# 1_0v.net
KiCad netlist of a schematic drawn in Altium Designer
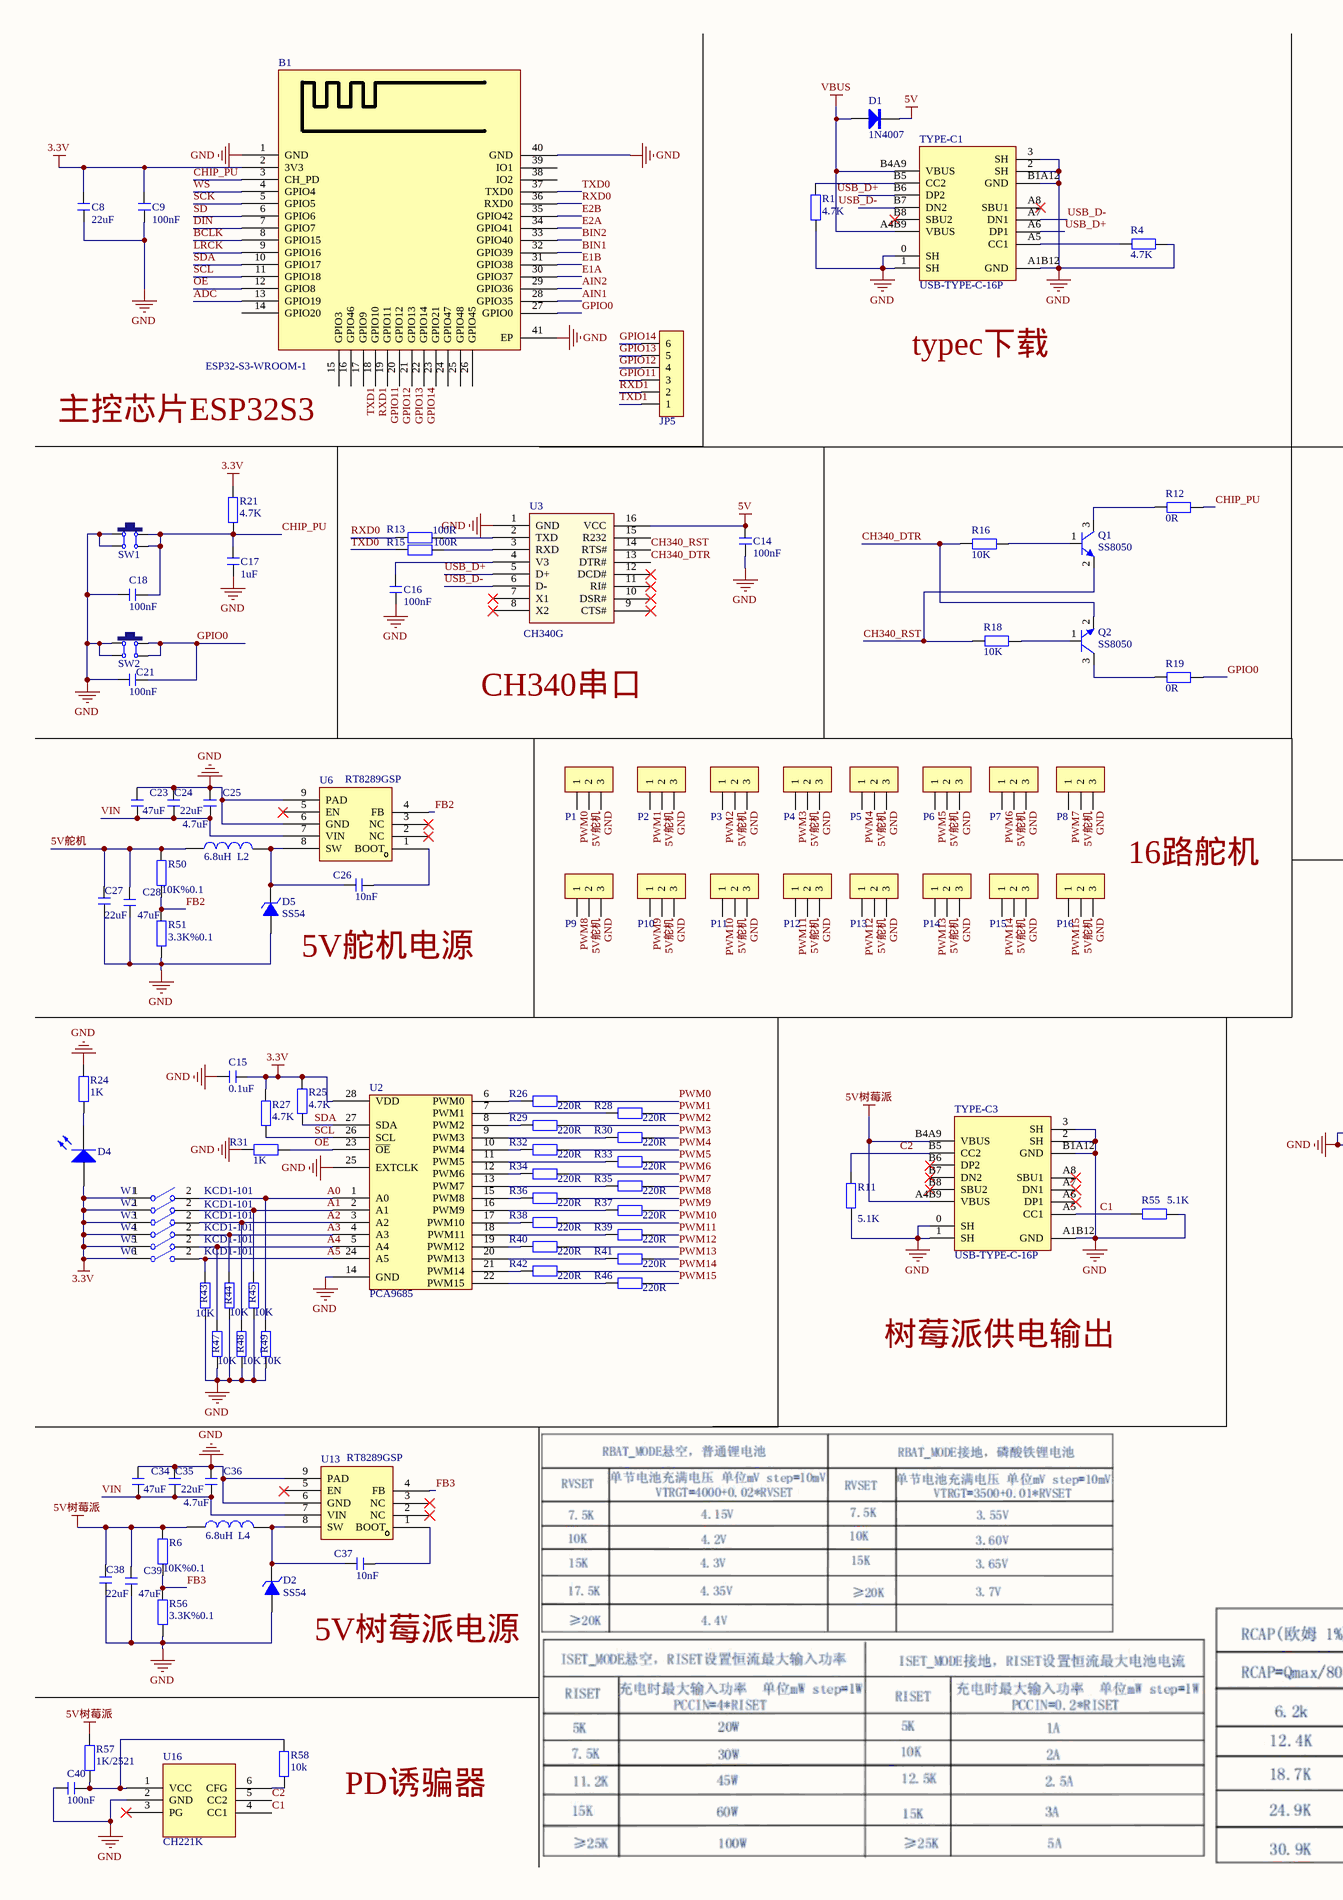
[diagram p0: 1.0v.SchDoc, left]
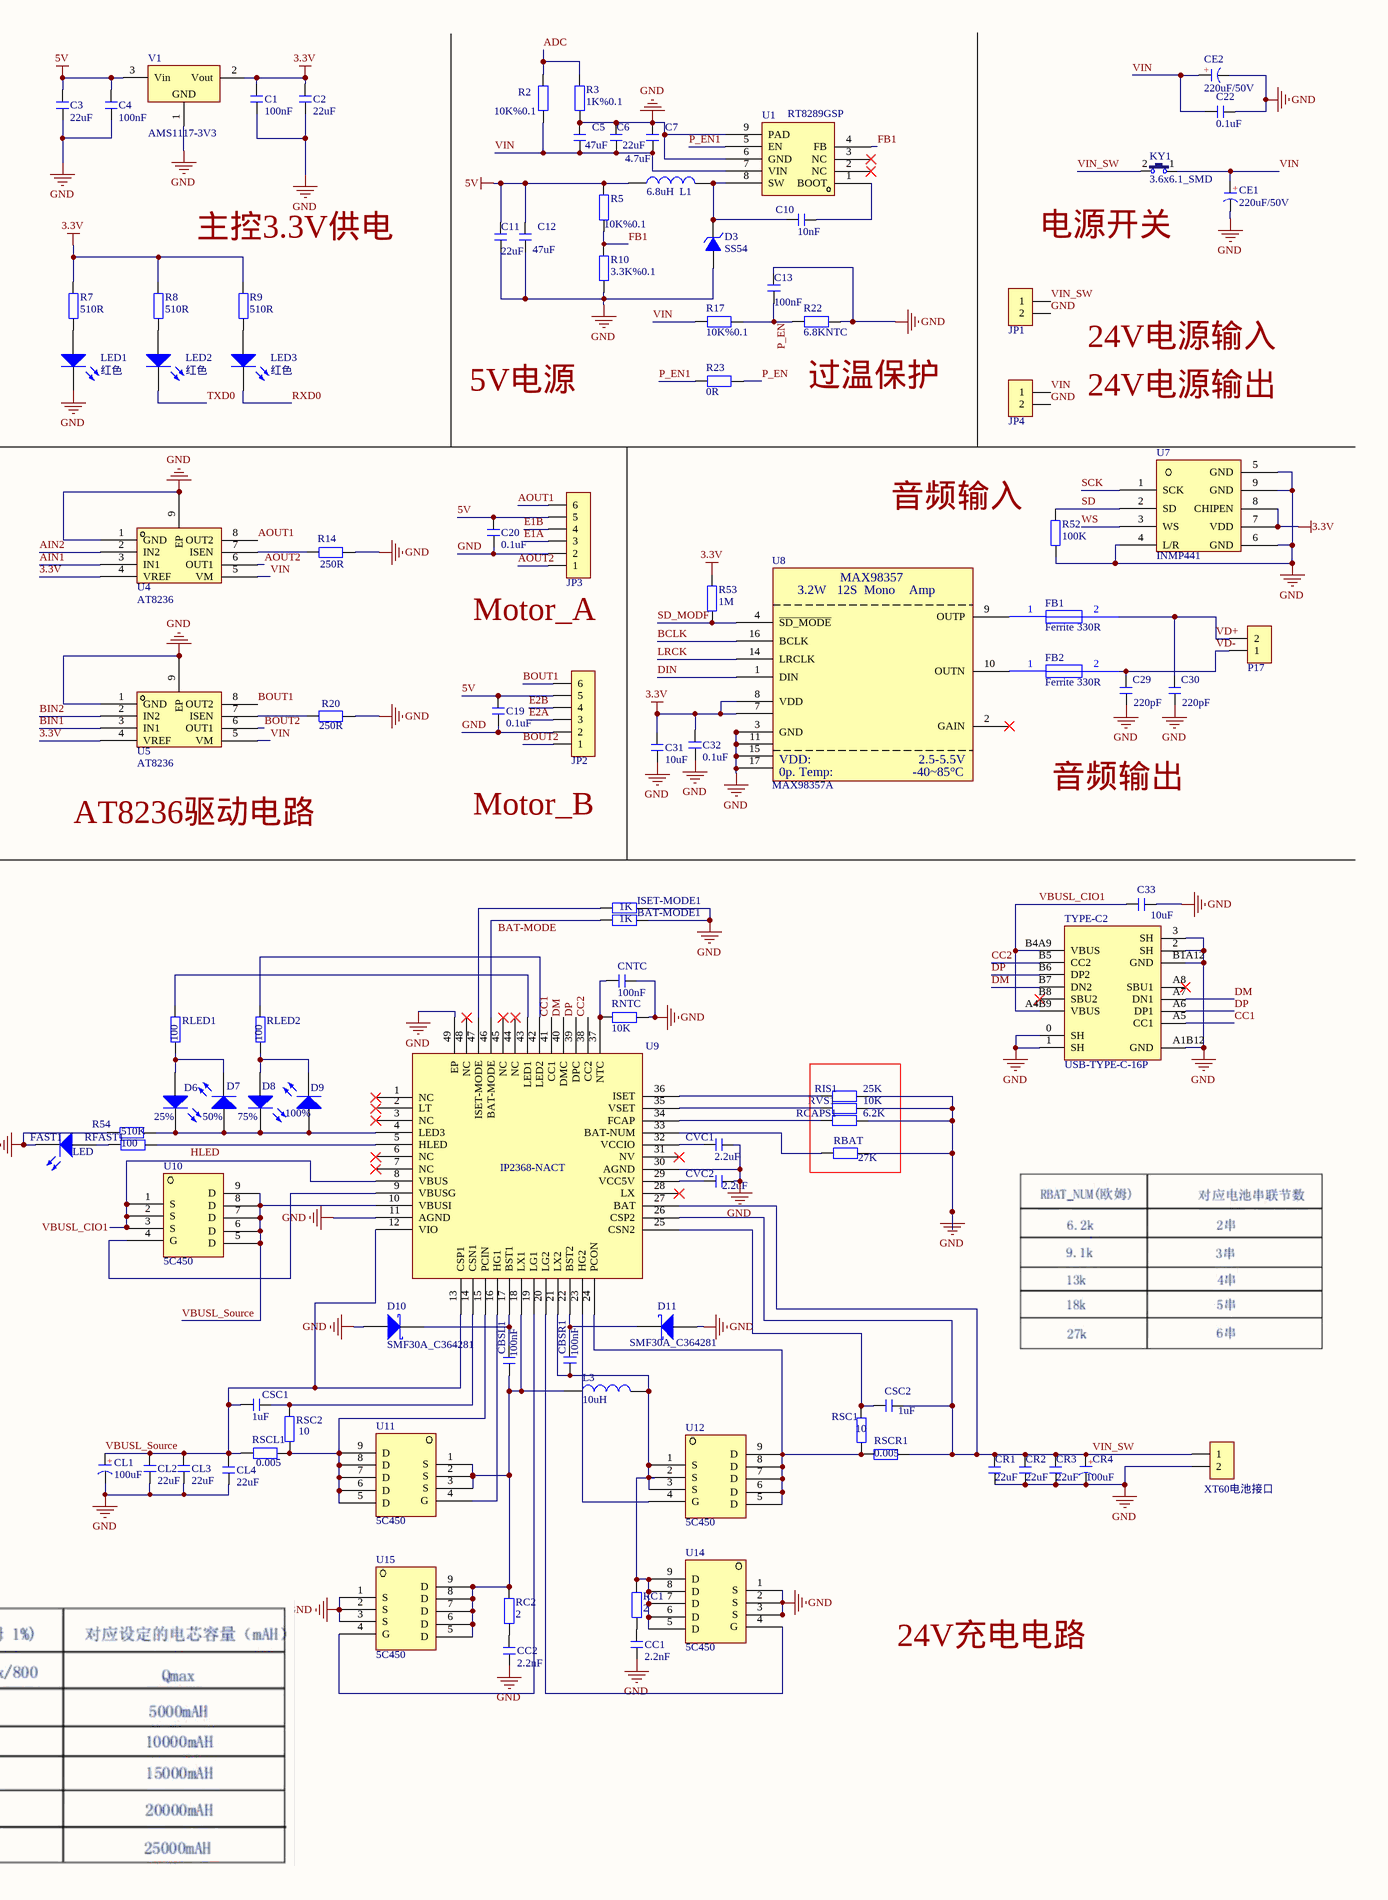
[diagram p1: 1.0v.SchDoc, right]

(export (version "E")
  (design (tool "Eeschema 10.0.6"))
  (components
    (comp (ref "B1")
      (value "ESP32-S3-WROOM-1")
      (footprint "WIFIM-SMD_ESP32-WROOM-32D")
      (libsource (lib "USB-C-12PIN") (part "ESP32-S3-WROOM-1"))
    )
    (comp (ref "BAT-MODE1")
      (value "1K")
      (footprint "R 0603_L")
      (description "贴片电阻")
      (fields (field (name "版权归属") "来自淘宝 ID：黄晶宝石"))
      (libsource (lib "0.1 - 电阻-电容-电感") (part "R"))
    )
    (comp (ref "C1")
      (value "100nF")
      (footprint "C 0603_L")
      (description "贴片电容")
      (libsource (lib "0.1 - 电阻-电容-电感") (part "C"))
    )
    (comp (ref "C2")
      (value "22uF")
      (footprint "C 0805_L")
      (description "贴片电容")
      (libsource (lib "0.1 - 电阻-电容-电感") (part "C"))
    )
    (comp (ref "C3")
      (value "22uF")
      (footprint "C 0805_L")
      (description "贴片电容")
      (libsource (lib "0.1 - 电阻-电容-电感") (part "C"))
    )
    (comp (ref "C4")
      (value "100nF")
      (footprint "C 0603_L")
      (description "贴片电容")
      (libsource (lib "0.1 - 电阻-电容-电感") (part "C"))
    )
    (comp (ref "C5")
      (value "47uF")
      (footprint "C 1210_L")
      (description "贴片电容")
      (libsource (lib "0.1 - 电阻-电容-电感") (part "C"))
    )
    (comp (ref "C6")
      (value "22uF")
      (footprint "C 1210_L")
      (description "贴片电容")
      (libsource (lib "0.1 - 电阻-电容-电感") (part "C"))
    )
    (comp (ref "C7")
      (value "4.7uF")
      (footprint "C 0603_L")
      (description "贴片电容")
      (libsource (lib "0.1 - 电阻-电容-电感") (part "C"))
    )
    (comp (ref "C8")
      (value "22uF")
      (footprint "C 0805_L")
      (description "贴片电容")
      (libsource (lib "0.1 - 电阻-电容-电感") (part "C"))
    )
    (comp (ref "C9")
      (value "100nF")
      (footprint "C 0603_L")
      (description "贴片电容")
      (libsource (lib "0.1 - 电阻-电容-电感") (part "C"))
    )
    (comp (ref "C10")
      (value "10nF")
      (footprint "C 0603_L")
      (description "贴片电容")
      (libsource (lib "0.1 - 电阻-电容-电感") (part "C"))
    )
    (comp (ref "C11")
      (value "22uF")
      (footprint "C 0805_L")
      (description "贴片电容")
      (libsource (lib "0.1 - 电阻-电容-电感") (part "C"))
    )
    (comp (ref "C12")
      (value "47uF")
      (footprint "C 0805_L")
      (description "贴片电容")
      (libsource (lib "0.1 - 电阻-电容-电感") (part "C"))
    )
    (comp (ref "C13")
      (value "100nF")
      (footprint "C 0603_L")
      (description "贴片电容")
      (libsource (lib "0.1 - 电阻-电容-电感") (part "C"))
    )
    (comp (ref "C14")
      (value "100nF")
      (footprint "C 0603_L")
      (description "贴片电容")
      (libsource (lib "0.1 - 电阻-电容-电感") (part "C"))
    )
    (comp (ref "C15")
      (value "0.1uF")
      (footprint "C 0603_L")
      (description "贴片电容")
      (libsource (lib "0.1 - 电阻-电容-电感") (part "C"))
    )
    (comp (ref "C16")
      (value "100nF")
      (footprint "C 0603_L")
      (description "贴片电容")
      (libsource (lib "0.1 - 电阻-电容-电感") (part "C"))
    )
    (comp (ref "C17")
      (value "1uF")
      (footprint "C 0603_L")
      (description "贴片电容")
      (libsource (lib "0.1 - 电阻-电容-电感") (part "C"))
    )
    (comp (ref "C18")
      (value "100nF")
      (footprint "C 0603_L")
      (description "贴片电容")
      (libsource (lib "0.1 - 电阻-电容-电感") (part "C"))
    )
    (comp (ref "C19")
      (value "0.1uF")
      (footprint "C 0603_L")
      (description "贴片电容")
      (libsource (lib "0.1 - 电阻-电容-电感") (part "C"))
    )
    (comp (ref "C20")
      (value "0.1uF")
      (footprint "C 0603_L")
      (description "贴片电容")
      (libsource (lib "0.1 - 电阻-电容-电感") (part "C"))
    )
    (comp (ref "C21")
      (value "100nF")
      (footprint "C 0603_L")
      (description "贴片电容")
      (libsource (lib "0.1 - 电阻-电容-电感") (part "C"))
    )
    (comp (ref "C22")
      (value "0.1uF")
      (footprint "C 0603_L")
      (description "贴片电容")
      (libsource (lib "0.1 - 电阻-电容-电感") (part "C"))
    )
    (comp (ref "C23")
      (value "47uF")
      (footprint "C 1210_L")
      (description "贴片电容")
      (libsource (lib "0.1 - 电阻-电容-电感") (part "C"))
    )
    (comp (ref "C24")
      (value "22uF")
      (footprint "C 1210_L")
      (description "贴片电容")
      (libsource (lib "0.1 - 电阻-电容-电感") (part "C"))
    )
    (comp (ref "C25")
      (value "4.7uF")
      (footprint "C 0603_L")
      (description "贴片电容")
      (libsource (lib "0.1 - 电阻-电容-电感") (part "C"))
    )
    (comp (ref "C26")
      (value "10nF")
      (footprint "C 0603_L")
      (description "贴片电容")
      (libsource (lib "0.1 - 电阻-电容-电感") (part "C"))
    )
    (comp (ref "C27")
      (value "22uF")
      (footprint "C 0805_L")
      (description "贴片电容")
      (libsource (lib "0.1 - 电阻-电容-电感") (part "C"))
    )
    (comp (ref "C28")
      (value "47uF")
      (footprint "C 0805_L")
      (description "贴片电容")
      (libsource (lib "0.1 - 电阻-电容-电感") (part "C"))
    )
    (comp (ref "C29")
      (value "220pF")
      (footprint "C 0603_L")
      (description "贴片电容")
      (libsource (lib "0.1 - 电阻-电容-电感") (part "C"))
    )
    (comp (ref "C30")
      (value "220pF")
      (footprint "C 0603_L")
      (description "贴片电容")
      (libsource (lib "0.1 - 电阻-电容-电感") (part "C"))
    )
    (comp (ref "C31")
      (value "10uF")
      (footprint "C 0603_L")
      (description "贴片电容")
      (libsource (lib "0.1 - 电阻-电容-电感") (part "C"))
    )
    (comp (ref "C32")
      (value "0.1uF")
      (footprint "C 0603_L")
      (description "贴片电容")
      (libsource (lib "0.1 - 电阻-电容-电感") (part "C"))
    )
    (comp (ref "C33")
      (value "10uF")
      (footprint "C 0603_L")
      (description "贴片电容")
      (libsource (lib "0.1 - 电阻-电容-电感") (part "C"))
    )
    (comp (ref "C34")
      (value "47uF")
      (footprint "C 1210_L")
      (description "贴片电容")
      (libsource (lib "0.1 - 电阻-电容-电感") (part "C"))
    )
    (comp (ref "C35")
      (value "22uF")
      (footprint "C 1210_L")
      (description "贴片电容")
      (libsource (lib "0.1 - 电阻-电容-电感") (part "C"))
    )
    (comp (ref "C36")
      (value "4.7uF")
      (footprint "C 0603_L")
      (description "贴片电容")
      (libsource (lib "0.1 - 电阻-电容-电感") (part "C"))
    )
    (comp (ref "C37")
      (value "10nF")
      (footprint "C 0603_L")
      (description "贴片电容")
      (libsource (lib "0.1 - 电阻-电容-电感") (part "C"))
    )
    (comp (ref "C38")
      (value "22uF")
      (footprint "C 0805_L")
      (description "贴片电容")
      (libsource (lib "0.1 - 电阻-电容-电感") (part "C"))
    )
    (comp (ref "C39")
      (value "47uF")
      (footprint "C 0805_L")
      (description "贴片电容")
      (libsource (lib "0.1 - 电阻-电容-电感") (part "C"))
    )
    (comp (ref "C40")
      (value "100nF")
      (footprint "C 0603_L")
      (description "贴片电容")
      (libsource (lib "0.1 - 电阻-电容-电感") (part "C"))
    )
    (comp (ref "CBSL1")
      (value "100nF")
      (footprint "C 0603_L")
      (description "贴片电容")
      (libsource (lib "0.1 - 电阻-电容-电感") (part "C"))
    )
    (comp (ref "CBSR1")
      (value "100nF")
      (footprint "C 0603_L")
      (description "贴片电容")
      (libsource (lib "0.1 - 电阻-电容-电感") (part "C"))
    )
    (comp (ref "CC1")
      (value "2.2nF")
      (footprint "C 0603_L")
      (description "贴片电容")
      (libsource (lib "0.1 - 电阻-电容-电感") (part "C"))
    )
    (comp (ref "CC2")
      (value "2.2nF")
      (footprint "C 0603_L")
      (description "贴片电容")
      (libsource (lib "0.1 - 电阻-电容-电感") (part "C"))
    )
    (comp (ref "CE1")
      (value "220uF/50V")
      (footprint "CM F(10*10.2)")
      (description "直插电解电容")
      (libsource (lib "0.1 - 电阻-电容-电感") (part "CE"))
    )
    (comp (ref "CE2")
      (value "220uF/50V")
      (footprint "CM F(10*10.2)")
      (description "直插电解电容")
      (libsource (lib "") (part "CE_1"))
    )
    (comp (ref "CL1")
      (value "100uF")
      (footprint "CM E(8*10.2)")
      (description "直插电解电容")
      (libsource (lib "0.1 - 电阻-电容-电感") (part "CE"))
    )
    (comp (ref "CL2")
      (value "22uF")
      (footprint "C 1210_L")
      (description "贴片电容")
      (libsource (lib "0.1 - 电阻-电容-电感") (part "C"))
    )
    (comp (ref "CL3")
      (value "22uF")
      (footprint "C 1210_L")
      (description "贴片电容")
      (libsource (lib "0.1 - 电阻-电容-电感") (part "C"))
    )
    (comp (ref "CL4")
      (value "22uF")
      (footprint "C 1210_L")
      (description "贴片电容")
      (libsource (lib "0.1 - 电阻-电容-电感") (part "C"))
    )
    (comp (ref "CNTC")
      (value "100nF")
      (footprint "C 0603_L")
      (description "贴片电容")
      (libsource (lib "0.1 - 电阻-电容-电感") (part "C"))
    )
    (comp (ref "CR1")
      (value "22uF")
      (footprint "C 1210_L")
      (description "贴片电容")
      (libsource (lib "0.1 - 电阻-电容-电感") (part "C"))
    )
    (comp (ref "CR2")
      (value "22uF")
      (footprint "C 1210_L")
      (description "贴片电容")
      (libsource (lib "0.1 - 电阻-电容-电感") (part "C"))
    )
    (comp (ref "CR3")
      (value "22uF")
      (footprint "C 1210_L")
      (description "贴片电容")
      (libsource (lib "0.1 - 电阻-电容-电感") (part "C"))
    )
    (comp (ref "CR4")
      (value "100uF")
      (footprint "CM E(8*10.2)")
      (description "直插电解电容")
      (libsource (lib "0.1 - 电阻-电容-电感") (part "CE"))
    )
    (comp (ref "CSC1")
      (value "1uF")
      (footprint "C 0603_L")
      (description "贴片电容")
      (libsource (lib "0.1 - 电阻-电容-电感") (part "C"))
    )
    (comp (ref "CSC2")
      (value "1uF")
      (footprint "C 0603_L")
      (description "贴片电容")
      (libsource (lib "0.1 - 电阻-电容-电感") (part "C"))
    )
    (comp (ref "CVC1")
      (value "2.2uF")
      (footprint "C 0603_L")
      (description "贴片电容")
      (libsource (lib "0.1 - 电阻-电容-电感") (part "C"))
    )
    (comp (ref "CVC2")
      (value "2.2uF")
      (footprint "C 0603_L")
      (description "贴片电容")
      (libsource (lib "0.1 - 电阻-电容-电感") (part "C"))
    )
    (comp (ref "D1")
      (value "1N4007")
      (footprint "SMA")
      (description "整流二极管")
      (libsource (lib "0.2 - 二极管-整流桥") (part "1N4007"))
    )
    (comp (ref "D2")
      (value "SS54")
      (footprint "SMA")
      (description "12V/0.5W稳压管")
      (fields (field (name "版权归属") "封装库来自淘宝 ID：黄晶宝石"))
      (libsource (lib "0.2 - 二极管-整流桥") (part "1N4106"))
    )
    (comp (ref "D3")
      (value "SS54")
      (footprint "SMA")
      (description "12V/0.5W稳压管")
      (fields (field (name "版权归属") "封装库来自淘宝 ID：黄晶宝石"))
      (libsource (lib "0.2 - 二极管-整流桥") (part "1N4106"))
    )
    (comp (ref "D4")
      (value "LED")
      (footprint "LED 0603G")
      (description "发光二极管")
      (fields (field (name "版权归属") "封装库来自淘宝 ID：黄晶宝石"))
      (libsource (lib "0.3 - LED发光二极管") (part "LED"))
    )
    (comp (ref "D5")
      (value "SS54")
      (footprint "SMA")
      (description "12V/0.5W稳压管")
      (fields (field (name "版权归属") "封装库来自淘宝 ID：黄晶宝石"))
      (libsource (lib "0.2 - 二极管-整流桥") (part "1N4106"))
    )
    (comp (ref "D6")
      (value "25%")
      (footprint "LED 0603G")
      (description "发光二极管")
      (fields (field (name "版权归属") "封装库来自淘宝 ID：黄晶宝石"))
      (libsource (lib "0.3 - LED发光二极管") (part "LED"))
    )
    (comp (ref "D7")
      (value "50%")
      (footprint "LED 0603G")
      (description "发光二极管")
      (fields (field (name "版权归属") "封装库来自淘宝 ID：黄晶宝石"))
      (libsource (lib "0.3 - LED发光二极管") (part "LED"))
    )
    (comp (ref "D8")
      (value "75%")
      (footprint "LED 0603G")
      (description "发光二极管")
      (fields (field (name "版权归属") "封装库来自淘宝 ID：黄晶宝石"))
      (libsource (lib "0.3 - LED发光二极管") (part "LED"))
    )
    (comp (ref "D9")
      (value "100%")
      (footprint "LED 0603G")
      (description "发光二极管")
      (fields (field (name "版权归属") "封装库来自淘宝 ID：黄晶宝石"))
      (libsource (lib "0.3 - LED发光二极管") (part "LED"))
    )
    (comp (ref "D10")
      (value "SMF30A_C364281")
      (footprint "SOD-123F")
      (description "肖特基二极管")
      (libsource (lib "0.2 - 二极管-整流桥") (part "SS14"))
    )
    (comp (ref "D11")
      (value "SMF30A_C364281")
      (footprint "SOD-123F")
      (description "肖特基二极管")
      (libsource (lib "0.2 - 二极管-整流桥") (part "SS14"))
    )
    (comp (ref "FAST1")
      (value "LED")
      (footprint "LED 0603G")
      (description "发光二极管")
      (fields (field (name "版权归属") "封装库来自淘宝 ID：黄晶宝石"))
      (libsource (lib "0.3 - LED发光二极管") (part "LED"))
    )
    (comp (ref "FB1")
      (value "Ferrite 330R")
      (footprint "R 0603_L")
      (libsource (lib "USB-C-12PIN") (part "Ferrite"))
    )
    (comp (ref "FB2")
      (value "Ferrite 330R")
      (footprint "R 0603_L")
      (libsource (lib "USB-C-12PIN") (part "Ferrite"))
    )
    (comp (ref "ISET-MODE1")
      (value "1K")
      (footprint "R 0603_L")
      (description "贴片电阻")
      (fields (field (name "版权归属") "来自淘宝 ID：黄晶宝石"))
      (libsource (lib "0.1 - 电阻-电容-电感") (part "R"))
    )
    (comp (ref "JP1")
      (value "HDR-1X2")
      (footprint "HDR2.54-M-LI-2P")
      (description "2P接插件")
      (fields (field (name "版权归属") "封装库来自淘宝 ID：黄晶宝石"))
      (libsource (lib "5.4 - 接插件-脚距2.54 (100mil) ") (part "Header 2"))
    )
    (comp (ref "JP2")
      (value "HDR-1X6")
      (footprint "HDR2.54-M-LI-6P")
      (description "6P接插件")
      (fields (field (name "版权归属") "封装库来自淘宝 ID：黄晶宝石"))
      (libsource (lib "5.4 - 接插件-脚距2.54 (100mil) ") (part "Header 6"))
    )
    (comp (ref "JP3")
      (value "HDR-1X6")
      (footprint "HDR2.54-M-LI-6P")
      (description "6P接插件")
      (fields (field (name "版权归属") "封装库来自淘宝 ID：黄晶宝石"))
      (libsource (lib "5.4 - 接插件-脚距2.54 (100mil) ") (part "Header 6"))
    )
    (comp (ref "JP4")
      (value "HDR-1X2")
      (footprint "HDR2.54-M-LI-2P")
      (description "2P接插件")
      (fields (field (name "版权归属") "封装库来自淘宝 ID：黄晶宝石"))
      (libsource (lib "5.4 - 接插件-脚距2.54 (100mil) ") (part "Header 2"))
    )
    (comp (ref "JP5")
      (value "HDR-1X6")
      (footprint "HDR2.54-M-LI-6P")
      (description "6P接插件")
      (fields (field (name "版权归属") "封装库来自淘宝 ID：黄晶宝石"))
      (libsource (lib "5.4 - 接插件-脚距2.54 (100mil) ") (part "Header 6"))
    )
    (comp (ref "KY1")
      (value "3.6x6.1_SMD")
      (footprint "SS-12F23")
      (description "侧按直插6x6轻触开关")
      (fields (field (name "版权归属") "封装库来自淘宝 ID：黄晶宝石"))
      (libsource (lib "0.7 - 常用按键-开关") (part "TSW DIP-6x6_V"))
    )
    (comp (ref "L1")
      (value "6.8uH")
      (footprint "CD73")
      (description "色环电感")
      (libsource (lib "0.1 - 电阻-电容-电感") (part "L-AL"))
    )
    (comp (ref "L2")
      (value "6.8uH")
      (footprint "CD73")
      (description "色环电感")
      (libsource (lib "0.1 - 电阻-电容-电感") (part "L-AL"))
    )
    (comp (ref "L3")
      (value "10uH")
      (footprint "PQ2012")
      (description "色环电感")
      (libsource (lib "0.1 - 电阻-电容-电感") (part "L-AL"))
    )
    (comp (ref "L4")
      (value "6.8uH")
      (footprint "CD73")
      (description "色环电感")
      (libsource (lib "0.1 - 电阻-电容-电感") (part "L-AL"))
    )
    (comp (ref "LED1")
      (value "红色")
      (footprint "LED 0603R")
      (description "直插5mm LED")
      (fields (field (name "版权归属") "封装库来自淘宝 ID：黄晶宝石"))
      (libsource (lib "0.3 - LED发光二极管") (part "LED-5MM"))
    )
    (comp (ref "LED2")
      (value "红色")
      (footprint "LED 0603R")
      (description "直插5mm LED")
      (fields (field (name "版权归属") "封装库来自淘宝 ID：黄晶宝石"))
      (libsource (lib "0.3 - LED发光二极管") (part "LED-5MM"))
    )
    (comp (ref "LED3")
      (value "红色")
      (footprint "LED 0603R")
      (description "直插5mm LED")
      (fields (field (name "版权归属") "封装库来自淘宝 ID：黄晶宝石"))
      (libsource (lib "0.3 - LED发光二极管") (part "LED-5MM"))
    )
    (comp (ref "P1")
      (value "HDR-1X3")
      (footprint "XH2.54-LI-3P")
      (description "3P接插件")
      (fields (field (name "版权归属") "封装库来自淘宝 ID：黄晶宝石"))
      (libsource (lib "5.4 - 接插件-脚距2.54 (100mil) ") (part "Header 3"))
    )
    (comp (ref "P2")
      (value "HDR-1X3")
      (footprint "XH2.54-LI-3P")
      (description "3P接插件")
      (fields (field (name "版权归属") "封装库来自淘宝 ID：黄晶宝石"))
      (libsource (lib "5.4 - 接插件-脚距2.54 (100mil) ") (part "Header 3"))
    )
    (comp (ref "P3")
      (value "HDR-1X3")
      (footprint "XH2.54-LI-3P")
      (description "3P接插件")
      (fields (field (name "版权归属") "封装库来自淘宝 ID：黄晶宝石"))
      (libsource (lib "5.4 - 接插件-脚距2.54 (100mil) ") (part "Header 3"))
    )
    (comp (ref "P4")
      (value "HDR-1X3")
      (footprint "XH2.54-LI-3P")
      (description "3P接插件")
      (fields (field (name "版权归属") "封装库来自淘宝 ID：黄晶宝石"))
      (libsource (lib "5.4 - 接插件-脚距2.54 (100mil) ") (part "Header 3"))
    )
    (comp (ref "P5")
      (value "HDR-1X3")
      (footprint "XH2.54-LI-3P")
      (description "3P接插件")
      (fields (field (name "版权归属") "封装库来自淘宝 ID：黄晶宝石"))
      (libsource (lib "5.4 - 接插件-脚距2.54 (100mil) ") (part "Header 3"))
    )
    (comp (ref "P6")
      (value "HDR-1X3")
      (footprint "XH2.54-LI-3P")
      (description "3P接插件")
      (fields (field (name "版权归属") "封装库来自淘宝 ID：黄晶宝石"))
      (libsource (lib "5.4 - 接插件-脚距2.54 (100mil) ") (part "Header 3"))
    )
    (comp (ref "P7")
      (value "HDR-1X3")
      (footprint "XH2.54-LI-3P")
      (description "3P接插件")
      (fields (field (name "版权归属") "封装库来自淘宝 ID：黄晶宝石"))
      (libsource (lib "5.4 - 接插件-脚距2.54 (100mil) ") (part "Header 3"))
    )
    (comp (ref "P8")
      (value "HDR-1X3")
      (footprint "XH2.54-LI-3P")
      (description "3P接插件")
      (fields (field (name "版权归属") "封装库来自淘宝 ID：黄晶宝石"))
      (libsource (lib "5.4 - 接插件-脚距2.54 (100mil) ") (part "Header 3"))
    )
    (comp (ref "P9")
      (value "HDR-1X3")
      (footprint "XH2.54-LI-3P")
      (description "3P接插件")
      (fields (field (name "版权归属") "封装库来自淘宝 ID：黄晶宝石"))
      (libsource (lib "5.4 - 接插件-脚距2.54 (100mil) ") (part "Header 3"))
    )
    (comp (ref "P10")
      (value "HDR-1X3")
      (footprint "XH2.54-LI-3P")
      (description "3P接插件")
      (fields (field (name "版权归属") "封装库来自淘宝 ID：黄晶宝石"))
      (libsource (lib "5.4 - 接插件-脚距2.54 (100mil) ") (part "Header 3"))
    )
    (comp (ref "P11")
      (value "HDR-1X3")
      (footprint "XH2.54-LI-3P")
      (description "3P接插件")
      (fields (field (name "版权归属") "封装库来自淘宝 ID：黄晶宝石"))
      (libsource (lib "5.4 - 接插件-脚距2.54 (100mil) ") (part "Header 3"))
    )
    (comp (ref "P12")
      (value "HDR-1X3")
      (footprint "XH2.54-LI-3P")
      (description "3P接插件")
      (fields (field (name "版权归属") "封装库来自淘宝 ID：黄晶宝石"))
      (libsource (lib "5.4 - 接插件-脚距2.54 (100mil) ") (part "Header 3"))
    )
    (comp (ref "P13")
      (value "HDR-1X3")
      (footprint "XH2.54-LI-3P")
      (description "3P接插件")
      (fields (field (name "版权归属") "封装库来自淘宝 ID：黄晶宝石"))
      (libsource (lib "5.4 - 接插件-脚距2.54 (100mil) ") (part "Header 3"))
    )
    (comp (ref "P14")
      (value "HDR-1X3")
      (footprint "XH2.54-LI-3P")
      (description "3P接插件")
      (fields (field (name "版权归属") "封装库来自淘宝 ID：黄晶宝石"))
      (libsource (lib "5.4 - 接插件-脚距2.54 (100mil) ") (part "Header 3"))
    )
    (comp (ref "P15")
      (value "HDR-1X3")
      (footprint "XH2.54-LI-3P")
      (description "3P接插件")
      (fields (field (name "版权归属") "封装库来自淘宝 ID：黄晶宝石"))
      (libsource (lib "5.4 - 接插件-脚距2.54 (100mil) ") (part "Header 3"))
    )
    (comp (ref "P16")
      (value "HDR-1X3")
      (footprint "XH2.54-LI-3P")
      (description "3P接插件")
      (fields (field (name "版权归属") "封装库来自淘宝 ID：黄晶宝石"))
      (libsource (lib "5.4 - 接插件-脚距2.54 (100mil) ") (part "Header 3"))
    )
    (comp (ref "P17")
      (value "HDR-1X2")
      (footprint "HDR2.54-M-LI-2P")
      (description "2P接插件")
      (fields (field (name "版权归属") "封装库来自淘宝 ID：黄晶宝石"))
      (libsource (lib "") (part "Header 2_2"))
    )
    (comp (ref "Q1")
      (value "SS8050")
      (footprint "SOT23")
      (description "高频放大-NPN型")
      (fields (field (name "版权归属") "封装库来自淘宝 ID：黄晶宝石"))
      (libsource (lib "0.4 - 三极管") (part "8050-SMD"))
    )
    (comp (ref "Q2")
      (value "SS8050")
      (footprint "SOT23")
      (description "高频放大-NPN型")
      (fields (field (name "版权归属") "封装库来自淘宝 ID：黄晶宝石"))
      (libsource (lib "0.4 - 三极管") (part "8050-SMD"))
    )
    (comp (ref "R1")
      (value "4.7K")
      (footprint "R 0603_L")
      (description "贴片电阻")
      (fields (field (name "版权归属") "来自淘宝 ID：黄晶宝石"))
      (libsource (lib "0.1 - 电阻-电容-电感") (part "R"))
    )
    (comp (ref "R2")
      (value "10K%0.1")
      (footprint "R 0603_L")
      (description "贴片电阻")
      (fields (field (name "版权归属") "来自淘宝 ID：黄晶宝石"))
      (libsource (lib "0.1 - 电阻-电容-电感") (part "R"))
    )
    (comp (ref "R3")
      (value "1K%0.1")
      (footprint "R 0603_L")
      (description "贴片电阻")
      (fields (field (name "版权归属") "来自淘宝 ID：黄晶宝石"))
      (libsource (lib "0.1 - 电阻-电容-电感") (part "R"))
    )
    (comp (ref "R4")
      (value "4.7K")
      (footprint "R 0603_L")
      (description "贴片电阻")
      (fields (field (name "版权归属") "来自淘宝 ID：黄晶宝石"))
      (libsource (lib "0.1 - 电阻-电容-电感") (part "R"))
    )
    (comp (ref "R5")
      (value "10K%0.1")
      (footprint "R 0603_L")
      (description "贴片电阻")
      (fields (field (name "版权归属") "来自淘宝 ID：黄晶宝石"))
      (libsource (lib "0.1 - 电阻-电容-电感") (part "R"))
    )
    (comp (ref "R6")
      (value "10K%0.1")
      (footprint "R 0603_L")
      (description "贴片电阻")
      (fields (field (name "版权归属") "来自淘宝 ID：黄晶宝石"))
      (libsource (lib "0.1 - 电阻-电容-电感") (part "R"))
    )
    (comp (ref "R7")
      (value "510R")
      (footprint "R 0603_L")
      (description "贴片电阻")
      (fields (field (name "版权归属") "来自淘宝 ID：黄晶宝石"))
      (libsource (lib "0.1 - 电阻-电容-电感") (part "R"))
    )
    (comp (ref "R8")
      (value "510R")
      (footprint "R 0603_L")
      (description "贴片电阻")
      (fields (field (name "版权归属") "来自淘宝 ID：黄晶宝石"))
      (libsource (lib "0.1 - 电阻-电容-电感") (part "R"))
    )
    (comp (ref "R9")
      (value "510R")
      (footprint "R 0603_L")
      (description "贴片电阻")
      (fields (field (name "版权归属") "来自淘宝 ID：黄晶宝石"))
      (libsource (lib "0.1 - 电阻-电容-电感") (part "R"))
    )
    (comp (ref "R10")
      (value "3.3K%0.1")
      (footprint "R 0603_L")
      (description "贴片电阻")
      (fields (field (name "版权归属") "来自淘宝 ID：黄晶宝石"))
      (libsource (lib "0.1 - 电阻-电容-电感") (part "R"))
    )
    (comp (ref "R11")
      (value "5.1K")
      (footprint "R 0603_L")
      (description "贴片电阻")
      (fields (field (name "版权归属") "来自淘宝 ID：黄晶宝石"))
      (libsource (lib "0.1 - 电阻-电容-电感") (part "R"))
    )
    (comp (ref "R12")
      (value "0R")
      (footprint "R 0603_L")
      (description "贴片电阻")
      (fields (field (name "版权归属") "来自淘宝 ID：黄晶宝石"))
      (libsource (lib "0.1 - 电阻-电容-电感") (part "R"))
    )
    (comp (ref "R13")
      (value "100R")
      (footprint "R 0603_L")
      (description "贴片电阻")
      (fields (field (name "版权归属") "来自淘宝 ID：黄晶宝石"))
      (libsource (lib "0.1 - 电阻-电容-电感") (part "R"))
    )
    (comp (ref "R14")
      (value "250R")
      (footprint "R 0603_L")
      (description "贴片电阻")
      (fields (field (name "版权归属") "来自淘宝 ID：黄晶宝石"))
      (libsource (lib "0.1 - 电阻-电容-电感") (part "R"))
    )
    (comp (ref "R15")
      (value "100R")
      (footprint "R 0603_L")
      (description "贴片电阻")
      (fields (field (name "版权归属") "来自淘宝 ID：黄晶宝石"))
      (libsource (lib "0.1 - 电阻-电容-电感") (part "R"))
    )
    (comp (ref "R16")
      (value "10K")
      (footprint "R 0603_L")
      (description "贴片电阻")
      (fields (field (name "版权归属") "来自淘宝 ID：黄晶宝石"))
      (libsource (lib "0.1 - 电阻-电容-电感") (part "R"))
    )
    (comp (ref "R17")
      (value "10K%0.1")
      (footprint "R 0603_L")
      (description "贴片电阻")
      (fields (field (name "版权归属") "来自淘宝 ID：黄晶宝石"))
      (libsource (lib "0.1 - 电阻-电容-电感") (part "R"))
    )
    (comp (ref "R18")
      (value "10K")
      (footprint "R 0603_L")
      (description "贴片电阻")
      (fields (field (name "版权归属") "来自淘宝 ID：黄晶宝石"))
      (libsource (lib "0.1 - 电阻-电容-电感") (part "R"))
    )
    (comp (ref "R19")
      (value "0R")
      (footprint "R 0603_L")
      (description "贴片电阻")
      (fields (field (name "版权归属") "来自淘宝 ID：黄晶宝石"))
      (libsource (lib "0.1 - 电阻-电容-电感") (part "R"))
    )
    (comp (ref "R20")
      (value "250R")
      (footprint "R 0603_L")
      (description "贴片电阻")
      (fields (field (name "版权归属") "来自淘宝 ID：黄晶宝石"))
      (libsource (lib "0.1 - 电阻-电容-电感") (part "R"))
    )
    (comp (ref "R21")
      (value "4.7K")
      (footprint "R 0603_L")
      (description "贴片电阻")
      (fields (field (name "版权归属") "来自淘宝 ID：黄晶宝石"))
      (libsource (lib "0.1 - 电阻-电容-电感") (part "R"))
    )
    (comp (ref "R22")
      (value "6.8KNTC")
      (footprint "R 0603_L")
      (description "贴片电阻")
      (fields (field (name "版权归属") "来自淘宝 ID：黄晶宝石"))
      (libsource (lib "0.1 - 电阻-电容-电感") (part "R"))
    )
    (comp (ref "R23")
      (value "0R")
      (footprint "R 0603_L")
      (description "贴片电阻")
      (fields (field (name "版权归属") "来自淘宝 ID：黄晶宝石"))
      (libsource (lib "0.1 - 电阻-电容-电感") (part "R"))
    )
    (comp (ref "R24")
      (value "1K")
      (footprint "R 0603_L")
      (description "贴片电阻")
      (fields (field (name "版权归属") "来自淘宝 ID：黄晶宝石"))
      (libsource (lib "0.1 - 电阻-电容-电感") (part "R"))
    )
    (comp (ref "R25")
      (value "4.7K")
      (footprint "R 0603_L")
      (description "贴片电阻")
      (fields (field (name "版权归属") "来自淘宝 ID：黄晶宝石"))
      (libsource (lib "0.1 - 电阻-电容-电感") (part "R"))
    )
    (comp (ref "R26")
      (value "220R")
      (footprint "R 0603_L")
      (description "贴片电阻")
      (fields (field (name "版权归属") "来自淘宝 ID：黄晶宝石"))
      (libsource (lib "0.1 - 电阻-电容-电感") (part "R"))
    )
    (comp (ref "R27")
      (value "4.7K")
      (footprint "R 0603_L")
      (description "贴片电阻")
      (fields (field (name "版权归属") "来自淘宝 ID：黄晶宝石"))
      (libsource (lib "0.1 - 电阻-电容-电感") (part "R"))
    )
    (comp (ref "R28")
      (value "220R")
      (footprint "R 0603_L")
      (description "贴片电阻")
      (fields (field (name "版权归属") "来自淘宝 ID：黄晶宝石"))
      (libsource (lib "0.1 - 电阻-电容-电感") (part "R"))
    )
    (comp (ref "R29")
      (value "220R")
      (footprint "R 0603_L")
      (description "贴片电阻")
      (fields (field (name "版权归属") "来自淘宝 ID：黄晶宝石"))
      (libsource (lib "0.1 - 电阻-电容-电感") (part "R"))
    )
    (comp (ref "R30")
      (value "220R")
      (footprint "R 0603_L")
      (description "贴片电阻")
      (fields (field (name "版权归属") "来自淘宝 ID：黄晶宝石"))
      (libsource (lib "0.1 - 电阻-电容-电感") (part "R"))
    )
    (comp (ref "R31")
      (value "1K")
      (footprint "R 0603_L")
      (description "贴片电阻")
      (fields (field (name "版权归属") "来自淘宝 ID：黄晶宝石"))
      (libsource (lib "0.1 - 电阻-电容-电感") (part "R"))
    )
    (comp (ref "R32")
      (value "220R")
      (footprint "R 0603_L")
      (description "贴片电阻")
      (fields (field (name "版权归属") "来自淘宝 ID：黄晶宝石"))
      (libsource (lib "0.1 - 电阻-电容-电感") (part "R"))
    )
    (comp (ref "R33")
      (value "220R")
      (footprint "R 0603_L")
      (description "贴片电阻")
      (fields (field (name "版权归属") "来自淘宝 ID：黄晶宝石"))
      (libsource (lib "0.1 - 电阻-电容-电感") (part "R"))
    )
    (comp (ref "R34")
      (value "220R")
      (footprint "R 0603_L")
      (description "贴片电阻")
      (fields (field (name "版权归属") "来自淘宝 ID：黄晶宝石"))
      (libsource (lib "0.1 - 电阻-电容-电感") (part "R"))
    )
    (comp (ref "R35")
      (value "220R")
      (footprint "R 0603_L")
      (description "贴片电阻")
      (fields (field (name "版权归属") "来自淘宝 ID：黄晶宝石"))
      (libsource (lib "0.1 - 电阻-电容-电感") (part "R"))
    )
    (comp (ref "R36")
      (value "220R")
      (footprint "R 0603_L")
      (description "贴片电阻")
      (fields (field (name "版权归属") "来自淘宝 ID：黄晶宝石"))
      (libsource (lib "0.1 - 电阻-电容-电感") (part "R"))
    )
    (comp (ref "R37")
      (value "220R")
      (footprint "R 0603_L")
      (description "贴片电阻")
      (fields (field (name "版权归属") "来自淘宝 ID：黄晶宝石"))
      (libsource (lib "0.1 - 电阻-电容-电感") (part "R"))
    )
    (comp (ref "R38")
      (value "220R")
      (footprint "R 0603_L")
      (description "贴片电阻")
      (fields (field (name "版权归属") "来自淘宝 ID：黄晶宝石"))
      (libsource (lib "0.1 - 电阻-电容-电感") (part "R"))
    )
    (comp (ref "R39")
      (value "220R")
      (footprint "R 0603_L")
      (description "贴片电阻")
      (fields (field (name "版权归属") "来自淘宝 ID：黄晶宝石"))
      (libsource (lib "0.1 - 电阻-电容-电感") (part "R"))
    )
    (comp (ref "R40")
      (value "220R")
      (footprint "R 0603_L")
      (description "贴片电阻")
      (fields (field (name "版权归属") "来自淘宝 ID：黄晶宝石"))
      (libsource (lib "0.1 - 电阻-电容-电感") (part "R"))
    )
    (comp (ref "R41")
      (value "220R")
      (footprint "R 0603_L")
      (description "贴片电阻")
      (fields (field (name "版权归属") "来自淘宝 ID：黄晶宝石"))
      (libsource (lib "0.1 - 电阻-电容-电感") (part "R"))
    )
    (comp (ref "R42")
      (value "220R")
      (footprint "R 0603_L")
      (description "贴片电阻")
      (fields (field (name "版权归属") "来自淘宝 ID：黄晶宝石"))
      (libsource (lib "0.1 - 电阻-电容-电感") (part "R"))
    )
    (comp (ref "R43")
      (value "10K")
      (footprint "R 0603_L")
      (description "贴片电阻")
      (fields (field (name "版权归属") "来自淘宝 ID：黄晶宝石"))
      (libsource (lib "0.1 - 电阻-电容-电感") (part "R"))
    )
    (comp (ref "R44")
      (value "10K")
      (footprint "R 0603_L")
      (description "贴片电阻")
      (fields (field (name "版权归属") "来自淘宝 ID：黄晶宝石"))
      (libsource (lib "0.1 - 电阻-电容-电感") (part "R"))
    )
    (comp (ref "R45")
      (value "10K")
      (footprint "R 0603_L")
      (description "贴片电阻")
      (fields (field (name "版权归属") "来自淘宝 ID：黄晶宝石"))
      (libsource (lib "0.1 - 电阻-电容-电感") (part "R"))
    )
    (comp (ref "R46")
      (value "220R")
      (footprint "R 0603_L")
      (description "贴片电阻")
      (fields (field (name "版权归属") "来自淘宝 ID：黄晶宝石"))
      (libsource (lib "0.1 - 电阻-电容-电感") (part "R"))
    )
    (comp (ref "R47")
      (value "10K")
      (footprint "R 0603_L")
      (description "贴片电阻")
      (fields (field (name "版权归属") "来自淘宝 ID：黄晶宝石"))
      (libsource (lib "0.1 - 电阻-电容-电感") (part "R"))
    )
    (comp (ref "R48")
      (value "10K")
      (footprint "R 0603_L")
      (description "贴片电阻")
      (fields (field (name "版权归属") "来自淘宝 ID：黄晶宝石"))
      (libsource (lib "0.1 - 电阻-电容-电感") (part "R"))
    )
    (comp (ref "R49")
      (value "10K")
      (footprint "R 0603_L")
      (description "贴片电阻")
      (fields (field (name "版权归属") "来自淘宝 ID：黄晶宝石"))
      (libsource (lib "0.1 - 电阻-电容-电感") (part "R"))
    )
    (comp (ref "R50")
      (value "10K%0.1")
      (footprint "R 0603_L")
      (description "贴片电阻")
      (fields (field (name "版权归属") "来自淘宝 ID：黄晶宝石"))
      (libsource (lib "0.1 - 电阻-电容-电感") (part "R"))
    )
    (comp (ref "R51")
      (value "3.3K%0.1")
      (footprint "R 0603_L")
      (description "贴片电阻")
      (fields (field (name "版权归属") "来自淘宝 ID：黄晶宝石"))
      (libsource (lib "0.1 - 电阻-电容-电感") (part "R"))
    )
    (comp (ref "R52")
      (value "100K")
      (footprint "R 0603_L")
      (description "贴片电阻")
      (fields (field (name "版权归属") "来自淘宝 ID：黄晶宝石"))
      (libsource (lib "0.1 - 电阻-电容-电感") (part "R"))
    )
    (comp (ref "R53")
      (value "1M")
      (footprint "R 0603_L")
      (description "贴片电阻")
      (fields (field (name "版权归属") "来自淘宝 ID：黄晶宝石"))
      (libsource (lib "0.1 - 电阻-电容-电感") (part "R"))
    )
    (comp (ref "R54")
      (value "510K")
      (footprint "R 0603_L")
      (description "贴片电阻")
      (fields (field (name "版权归属") "来自淘宝 ID：黄晶宝石"))
      (libsource (lib "0.1 - 电阻-电容-电感") (part "R"))
    )
    (comp (ref "R55")
      (value "5.1K")
      (footprint "R 0603_L")
      (description "贴片电阻")
      (fields (field (name "版权归属") "来自淘宝 ID：黄晶宝石"))
      (libsource (lib "0.1 - 电阻-电容-电感") (part "R"))
    )
    (comp (ref "R56")
      (value "3.3K%0.1")
      (footprint "R 0603_L")
      (description "贴片电阻")
      (fields (field (name "版权归属") "来自淘宝 ID：黄晶宝石"))
      (libsource (lib "0.1 - 电阻-电容-电感") (part "R"))
    )
    (comp (ref "R57")
      (value "1K/2521")
      (footprint "R 2512_L")
      (description "贴片电阻")
      (fields (field (name "版权归属") "来自淘宝 ID：黄晶宝石"))
      (libsource (lib "0.1 - 电阻-电容-电感") (part "R"))
    )
    (comp (ref "R58")
      (value "10k")
      (footprint "R 0603_L")
      (description "贴片电阻")
      (fields (field (name "版权归属") "来自淘宝 ID：黄晶宝石"))
      (libsource (lib "0.1 - 电阻-电容-电感") (part "R"))
    )
    (comp (ref "RBAT")
      (value "27K")
      (footprint "R 0603_L")
      (description "贴片电阻")
      (fields (field (name "版权归属") "来自淘宝 ID：黄晶宝石"))
      (libsource (lib "0.1 - 电阻-电容-电感") (part "R"))
    )
    (comp (ref "RC1")
      (value "2")
      (footprint "R 0603_L")
      (description "贴片电阻")
      (fields (field (name "版权归属") "来自淘宝 ID：黄晶宝石"))
      (libsource (lib "0.1 - 电阻-电容-电感") (part "R"))
    )
    (comp (ref "RC2")
      (value "2")
      (footprint "R 0603_L")
      (description "贴片电阻")
      (fields (field (name "版权归属") "来自淘宝 ID：黄晶宝石"))
      (libsource (lib "0.1 - 电阻-电容-电感") (part "R"))
    )
    (comp (ref "RCAPS1")
      (value "6.2K")
      (footprint "R 0603_L")
      (description "贴片电阻")
      (fields (field (name "版权归属") "来自淘宝 ID：黄晶宝石"))
      (libsource (lib "0.1 - 电阻-电容-电感") (part "R"))
    )
    (comp (ref "RFAST1")
      (value "100")
      (footprint "R 0603_L")
      (description "贴片电阻")
      (fields (field (name "版权归属") "来自淘宝 ID：黄晶宝石"))
      (libsource (lib "0.1 - 电阻-电容-电感") (part "R"))
    )
    (comp (ref "RIS1")
      (value "25K")
      (footprint "R 0603_L")
      (description "贴片电阻")
      (fields (field (name "版权归属") "来自淘宝 ID：黄晶宝石"))
      (libsource (lib "0.1 - 电阻-电容-电感") (part "R"))
    )
    (comp (ref "RLED1")
      (value "100")
      (footprint "R 0603_L")
      (description "贴片电阻")
      (fields (field (name "版权归属") "来自淘宝 ID：黄晶宝石"))
      (libsource (lib "0.1 - 电阻-电容-电感") (part "R"))
    )
    (comp (ref "RLED2")
      (value "100")
      (footprint "R 0603_L")
      (description "贴片电阻")
      (fields (field (name "版权归属") "来自淘宝 ID：黄晶宝石"))
      (libsource (lib "0.1 - 电阻-电容-电感") (part "R"))
    )
    (comp (ref "RNTC")
      (value "10K")
      (footprint "R 0603_L")
      (description "贴片电阻")
      (fields (field (name "版权归属") "来自淘宝 ID：黄晶宝石"))
      (libsource (lib "0.1 - 电阻-电容-电感") (part "R"))
    )
    (comp (ref "RSC1")
      (value "10")
      (footprint "R 0603_L")
      (description "贴片电阻")
      (fields (field (name "版权归属") "来自淘宝 ID：黄晶宝石"))
      (libsource (lib "0.1 - 电阻-电容-电感") (part "R"))
    )
    (comp (ref "RSC2")
      (value "10")
      (footprint "R 0603_L")
      (description "贴片电阻")
      (fields (field (name "版权归属") "来自淘宝 ID：黄晶宝石"))
      (libsource (lib "0.1 - 电阻-电容-电感") (part "R"))
    )
    (comp (ref "RSCL1")
      (value "0.005")
      (footprint "R 2512_L")
      (description "贴片电阻")
      (fields (field (name "版权归属") "来自淘宝 ID：黄晶宝石"))
      (libsource (lib "0.1 - 电阻-电容-电感") (part "R"))
    )
    (comp (ref "RSCR1")
      (value "0.005")
      (footprint "R 2512_L")
      (description "贴片电阻")
      (fields (field (name "版权归属") "来自淘宝 ID：黄晶宝石"))
      (libsource (lib "0.1 - 电阻-电容-电感") (part "R"))
    )
    (comp (ref "RVS1")
      (value "10K")
      (footprint "R 0603_L")
      (description "贴片电阻")
      (fields (field (name "版权归属") "来自淘宝 ID：黄晶宝石"))
      (libsource (lib "0.1 - 电阻-电容-电感") (part "R"))
    )
    (comp (ref "SW1")
      (value "6x6x5")
      (footprint "TSW SMD-6*6*5")
      (description "直插6x6轻触开关")
      (fields (field (name "版权归属") "封装库来自淘宝 ID：黄晶宝石"))
      (libsource (lib "0.7 - 常用按键-开关") (part "TSW DIP-6x6"))
    )
    (comp (ref "SW2")
      (value "6x6x5")
      (footprint "TSW SMD-6*6*5")
      (description "直插6x6轻触开关")
      (fields (field (name "版权归属") "封装库来自淘宝 ID：黄晶宝石"))
      (libsource (lib "0.7 - 常用按键-开关") (part "TSW DIP-6x6"))
    )
    (comp (ref "TYPE-C1")
      (value "USB-TYPE-C-16P")
      (footprint "USB-C-SMD_TYPE-C16PIN-SHOUHAN")
      (libsource (lib "PCB_Project_1") (part "USB-TYPE-C"))
    )
    (comp (ref "TYPE-C2")
      (value "USB-TYPE-C-16P")
      (footprint "USB-C-SMD_TYPE-C16PIN-SHOUHAN")
      (libsource (lib "PCB_Project_1") (part "USB-TYPE-C"))
    )
    (comp (ref "TYPE-C3")
      (value "USB-TYPE-C-16P")
      (footprint "USB-C-SMD_TYPE-C16PIN-SHOUHAN")
      (libsource (lib "PCB_Project_1") (part "USB-TYPE-C"))
    )
    (comp (ref "U1")
      (value "RT8289GSP")
      (footprint "SOP8")
      (libsource (lib "USB-C-12PIN") (part "RT8289GSP"))
    )
    (comp (ref "U2")
      (value "PCA9685")
      (footprint "TSSOP-28")
      (libsource (lib "USB-C-12PIN") (part "PCA9685"))
    )
    (comp (ref "U3")
      (value "CH340G")
      (footprint "SOP16")
      (libsource (lib "1.9 - CH340系列编程器芯片") (part "CH340G"))
    )
    (comp (ref "U4") (value "AT8236") (footprint "SOP8") (libsource (lib "USB-C-12PIN") (part "AT8236")))
    (comp (ref "U5") (value "AT8236") (footprint "SOP8") (libsource (lib "USB-C-12PIN") (part "AT8236")))
    (comp (ref "U6")
      (value "RT8289GSP")
      (footprint "SOP8")
      (libsource (lib "USB-C-12PIN") (part "RT8289GSP"))
    )
    (comp (ref "U7") (value "INMP441") (footprint "INMP441") (libsource (lib "USB-C-12PIN") (part "121")))
    (comp (ref "U8")
      (value "MAX98357A")
      (footprint "QFN16")
      (libsource (lib "PCB_Project_1") (part "MAX98357A"))
    )
    (comp (ref "U9")
      (value "IP2368-NACT")
      (footprint "QFN48 7X7_L")
      (libsource (lib "USB-C-12PIN") (part "IP2368"))
    )
    (comp (ref "U10") (value "5C450") (footprint "5C450L") (libsource (lib "") (part "PK616BAQC_1")))
    (comp (ref "U11") (value "5C450") (footprint "5C450L") (libsource (lib "USB-C-12PIN") (part "PK616BAQC")))
    (comp (ref "U12") (value "5C450") (footprint "5C450L") (libsource (lib "") (part "PK616BAQC_1")))
    (comp (ref "U13")
      (value "RT8289GSP")
      (footprint "SOP8")
      (libsource (lib "USB-C-12PIN") (part "RT8289GSP"))
    )
    (comp (ref "U14") (value "5C450") (footprint "5C450L") (libsource (lib "USB-C-12PIN") (part "PK616BAQC")))
    (comp (ref "U15") (value "5C450") (footprint "5C450L") (libsource (lib "") (part "PK616BAQC_1")))
    (comp (ref "U16") (value "CH221K") (footprint "SOT23-6L") (libsource (lib "PCB_Project") (part "CH221K")))
    (comp (ref "V1")
      (value "AMS1117-3V3")
      (footprint "SOT-223")
      (description "三端稳压芯片")
      (libsource (lib "1.1 - 电源类芯片") (part "AMS1117"))
    )
    (comp (ref "W1")
      (value "KCD1-101")
      (footprint "R 0603_L")
      (description "1路单刀船型开关")
      (fields (field (name "版权归属") "封装库来自淘宝 ID：黄晶宝石"))
      (libsource (lib "0.7 - 常用按键-开关") (part "KCD1-101"))
    )
    (comp (ref "W2")
      (value "KCD1-101")
      (footprint "R 0603_L")
      (description "1路单刀船型开关")
      (fields (field (name "版权归属") "封装库来自淘宝 ID：黄晶宝石"))
      (libsource (lib "0.7 - 常用按键-开关") (part "KCD1-101"))
    )
    (comp (ref "W3")
      (value "KCD1-101")
      (footprint "R 0603_L")
      (description "1路单刀船型开关")
      (fields (field (name "版权归属") "封装库来自淘宝 ID：黄晶宝石"))
      (libsource (lib "0.7 - 常用按键-开关") (part "KCD1-101"))
    )
    (comp (ref "W4")
      (value "KCD1-101")
      (footprint "R 0603_L")
      (description "1路单刀船型开关")
      (fields (field (name "版权归属") "封装库来自淘宝 ID：黄晶宝石"))
      (libsource (lib "0.7 - 常用按键-开关") (part "KCD1-101"))
    )
    (comp (ref "W5")
      (value "KCD1-101")
      (footprint "R 0603_L")
      (description "1路单刀船型开关")
      (fields (field (name "版权归属") "封装库来自淘宝 ID：黄晶宝石"))
      (libsource (lib "0.7 - 常用按键-开关") (part "KCD1-101"))
    )
    (comp (ref "W6")
      (value "KCD1-101")
      (footprint "R 0603_L")
      (description "1路单刀船型开关")
      (fields (field (name "版权归属") "封装库来自淘宝 ID：黄晶宝石"))
      (libsource (lib "0.7 - 常用按键-开关") (part "KCD1-101"))
    )
    (comp (ref "XT60电池接口")
      (value "HDR-1X2")
      (footprint "TX60-LI-S")
      (description "2P接插件")
      (fields (field (name "版权归属") "封装库来自淘宝 ID：黄晶宝石"))
      (libsource (lib "") (part "Header 2_1"))
    )
  )
  (nets
    (net (code "1") (name "/5V舵机") (class "Default")
      (node (ref "C27") (pin "1") (pinfunction "1_1") (pintype "passive"))
      (node (ref "C28") (pin "1") (pinfunction "1_1") (pintype "passive"))
      (node (ref "L2") (pin "1") (pinfunction "1_1") (pintype "passive"))
      (node (ref "P1") (pin "2") (pinfunction "2_2") (pintype "passive"))
      (node (ref "P10") (pin "2") (pinfunction "2_2") (pintype "passive"))
      (node (ref "P11") (pin "2") (pinfunction "2_2") (pintype "passive"))
      (node (ref "P12") (pin "2") (pinfunction "2_2") (pintype "passive"))
      (node (ref "P13") (pin "2") (pinfunction "2_2") (pintype "passive"))
      (node (ref "P14") (pin "2") (pinfunction "2_2") (pintype "passive"))
      (node (ref "P15") (pin "2") (pinfunction "2_2") (pintype "passive"))
      (node (ref "P16") (pin "2") (pinfunction "2_2") (pintype "passive"))
      (node (ref "P2") (pin "2") (pinfunction "2_2") (pintype "passive"))
      (node (ref "P3") (pin "2") (pinfunction "2_2") (pintype "passive"))
      (node (ref "P4") (pin "2") (pinfunction "2_2") (pintype "passive"))
      (node (ref "P5") (pin "2") (pinfunction "2_2") (pintype "passive"))
      (node (ref "P6") (pin "2") (pinfunction "2_2") (pintype "passive"))
      (node (ref "P7") (pin "2") (pinfunction "2_2") (pintype "passive"))
      (node (ref "P8") (pin "2") (pinfunction "2_2") (pintype "passive"))
      (node (ref "P9") (pin "2") (pinfunction "2_2") (pintype "passive"))
      (node (ref "R50") (pin "1") (pinfunction "1_1") (pintype "passive"))
    )
    (net (code "2") (name "/A0") (class "Default")
      (node (ref "R49") (pin "2") (pinfunction "2_2") (pintype "passive"))
      (node (ref "U2") (pin "1") (pinfunction "A0_1") (pintype "passive"))
      (node (ref "W1") (pin "2") (pinfunction "2_2") (pintype "passive"))
    )
    (net (code "3") (name "/A1") (class "Default")
      (node (ref "R45") (pin "2") (pinfunction "2_2") (pintype "passive"))
      (node (ref "U2") (pin "2") (pinfunction "A1_2") (pintype "passive"))
      (node (ref "W2") (pin "2") (pinfunction "2_2") (pintype "passive"))
    )
    (net (code "4") (name "/A2") (class "Default")
      (node (ref "R48") (pin "2") (pinfunction "2_2") (pintype "passive"))
      (node (ref "U2") (pin "3") (pinfunction "A2_3") (pintype "passive"))
      (node (ref "W3") (pin "2") (pinfunction "2_2") (pintype "passive"))
    )
    (net (code "5") (name "/A3") (class "Default")
      (node (ref "R44") (pin "2") (pinfunction "2_2") (pintype "passive"))
      (node (ref "U2") (pin "4") (pinfunction "A3_4") (pintype "passive"))
      (node (ref "W4") (pin "2") (pinfunction "2_2") (pintype "passive"))
    )
    (net (code "6") (name "/A4") (class "Default")
      (node (ref "R47") (pin "2") (pinfunction "2_2") (pintype "passive"))
      (node (ref "U2") (pin "5") (pinfunction "A4_5") (pintype "passive"))
      (node (ref "W5") (pin "2") (pinfunction "2_2") (pintype "passive"))
    )
    (net (code "7") (name "/A5") (class "Default")
      (node (ref "R43") (pin "2") (pinfunction "2_2") (pintype "passive"))
      (node (ref "U2") (pin "24") (pinfunction "A5_24") (pintype "passive"))
      (node (ref "W6") (pin "2") (pinfunction "2_2") (pintype "passive"))
    )
    (net (code "8") (name "/ADC") (class "Default")
      (node (ref "B1") (pin "13") (pinfunction "GPIO19_13") (pintype "passive"))
      (node (ref "R2") (pin "1") (pinfunction "1_1") (pintype "passive"))
      (node (ref "R3") (pin "1") (pinfunction "1_1") (pintype "passive"))
    )
    (net (code "9") (name "/AIN1") (class "Default")
      (node (ref "B1") (pin "28") (pinfunction "GPIO35_28") (pintype "passive"))
      (node (ref "U4") (pin "3") (pinfunction "IN1_3") (pintype "passive"))
    )
    (net (code "10") (name "/AIN2") (class "Default")
      (node (ref "B1") (pin "29") (pinfunction "GPIO36_29") (pintype "passive"))
      (node (ref "U4") (pin "2") (pinfunction "IN2_2") (pintype "passive"))
    )
    (net (code "11") (name "/AOUT1") (class "Default")
      (node (ref "JP3") (pin "6") (pinfunction "6_6") (pintype "passive"))
      (node (ref "U4") (pin "8") (pinfunction "OUT2_8") (pintype "passive"))
    )
    (net (code "12") (name "/AOUT2") (class "Default")
      (node (ref "JP3") (pin "1") (pinfunction "1_1") (pintype "passive"))
      (node (ref "U4") (pin "6") (pinfunction "OUT1_6") (pintype "passive"))
    )
    (net (code "13") (name "/BAT-MODE") (class "Default")
      (node (ref "BAT-MODE1") (pin "1") (pinfunction "1_1") (pintype "passive"))
      (node (ref "U9") (pin "46") (pinfunction "BAT-MODE_46") (pintype "passive"))
    )
    (net (code "14") (name "/BCLK") (class "Default")
      (node (ref "B1") (pin "8") (pinfunction "GPIO15_8") (pintype "passive"))
      (node (ref "U8") (pin "16") (pinfunction "BCLK_16") (pintype "passive"))
    )
    (net (code "15") (name "/BIN1") (class "Default")
      (node (ref "B1") (pin "32") (pinfunction "GPIO39_32") (pintype "passive"))
      (node (ref "U5") (pin "3") (pinfunction "IN1_3") (pintype "passive"))
    )
    (net (code "16") (name "/BIN2") (class "Default")
      (node (ref "B1") (pin "33") (pinfunction "GPIO40_33") (pintype "passive"))
      (node (ref "U5") (pin "2") (pinfunction "IN2_2") (pintype "passive"))
    )
    (net (code "17") (name "/BOUT1") (class "Default")
      (node (ref "JP2") (pin "6") (pinfunction "6_6") (pintype "passive"))
      (node (ref "U5") (pin "8") (pinfunction "OUT2_8") (pintype "passive"))
    )
    (net (code "18") (name "/BOUT2") (class "Default")
      (node (ref "JP2") (pin "1") (pinfunction "1_1") (pintype "passive"))
      (node (ref "U5") (pin "6") (pinfunction "OUT1_6") (pintype "passive"))
    )
    (net (code "19") (name "/C1") (class "Default")
      (node (ref "R55") (pin "2") (pinfunction "2_2") (pintype "passive"))
      (node (ref "TYPE-C3") (pin "A5") (pinfunction "CC1_A5") (pintype "passive"))
      (node (ref "U16") (pin "4") (pinfunction "CC1_4") (pintype "passive"))
    )
    (net (code "20") (name "/C2") (class "Default")
      (node (ref "R11") (pin "2") (pinfunction "2_2") (pintype "passive"))
      (node (ref "TYPE-C3") (pin "B5") (pinfunction "CC2_B5") (pintype "passive"))
      (node (ref "U16") (pin "5") (pinfunction "CC2_5") (pintype "passive"))
    )
    (net (code "21") (name "/CC1") (class "Default")
      (node (ref "TYPE-C2") (pin "A5") (pinfunction "CC1_A5") (pintype "passive"))
      (node (ref "U9") (pin "41") (pinfunction "CC1_41") (pintype "passive"))
    )
    (net (code "22") (name "/CC2") (class "Default")
      (node (ref "TYPE-C2") (pin "B5") (pinfunction "CC2_B5") (pintype "passive"))
      (node (ref "U9") (pin "38") (pinfunction "CC2_38") (pintype "passive"))
    )
    (net (code "23") (name "/CH340_DTR") (class "Default")
      (node (ref "Q2") (pin "2") (pinfunction "E_2") (pintype "passive"))
      (node (ref "R16") (pin "2") (pinfunction "2_2") (pintype "passive"))
      (node (ref "U3") (pin "13") (pinfunction "DTR#_13") (pintype "passive"))
    )
    (net (code "24") (name "/CH340_RST") (class "Default")
      (node (ref "Q1") (pin "2") (pinfunction "E_2") (pintype "passive"))
      (node (ref "R18") (pin "2") (pinfunction "2_2") (pintype "passive"))
      (node (ref "U3") (pin "14") (pinfunction "RTS#_14") (pintype "passive"))
    )
    (net (code "25") (name "/CHIP_PU") (class "Default")
      (node (ref "B1") (pin "3") (pinfunction "CH_PD_3") (pintype "passive"))
      (node (ref "C17") (pin "1") (pinfunction "1_1") (pintype "passive"))
      (node (ref "C18") (pin "1") (pinfunction "1_1") (pintype "passive"))
      (node (ref "R12") (pin "1") (pinfunction "1_1") (pintype "passive"))
      (node (ref "R21") (pin "1") (pinfunction "1_1") (pintype "passive"))
      (node (ref "SW1") (pin "2") (pinfunction "2_2") (pintype "passive"))
      (node (ref "SW1") (pin "3") (pinfunction "3_3") (pintype "passive"))
    )
    (net (code "26") (name "/DIN") (class "Default")
      (node (ref "B1") (pin "7") (pinfunction "GPIO7_7") (pintype "passive"))
      (node (ref "U8") (pin "1") (pinfunction "DIN_1") (pintype "passive"))
    )
    (net (code "27") (name "/DM") (class "Default")
      (node (ref "TYPE-C2") (pin "A7") (pinfunction "DN1_A7") (pintype "passive"))
      (node (ref "TYPE-C2") (pin "B7") (pinfunction "DN2_B7") (pintype "passive"))
      (node (ref "U9") (pin "40") (pinfunction "DMC_40") (pintype "passive"))
    )
    (net (code "28") (name "/DP") (class "Default")
      (node (ref "TYPE-C2") (pin "A6") (pinfunction "DP1_A6") (pintype "passive"))
      (node (ref "TYPE-C2") (pin "B6") (pinfunction "DP2_B6") (pintype "passive"))
      (node (ref "U9") (pin "39") (pinfunction "DPC_39") (pintype "passive"))
    )
    (net (code "29") (name "/E1A") (class "Default")
      (node (ref "B1") (pin "30") (pinfunction "GPIO37_30") (pintype "passive"))
      (node (ref "JP3") (pin "3") (pinfunction "3_3") (pintype "passive"))
    )
    (net (code "30") (name "/E1B") (class "Default")
      (node (ref "B1") (pin "31") (pinfunction "GPIO38_31") (pintype "passive"))
      (node (ref "JP3") (pin "4") (pinfunction "4_4") (pintype "passive"))
    )
    (net (code "31") (name "/E2A") (class "Default")
      (node (ref "B1") (pin "34") (pinfunction "GPIO41_34") (pintype "passive"))
      (node (ref "JP2") (pin "3") (pinfunction "3_3") (pintype "passive"))
    )
    (net (code "32") (name "/E2B") (class "Default")
      (node (ref "B1") (pin "35") (pinfunction "GPIO42_35") (pintype "passive"))
      (node (ref "JP2") (pin "4") (pinfunction "4_4") (pintype "passive"))
    )
    (net (code "33") (name "/FB1") (class "Default")
      (node (ref "R10") (pin "1") (pinfunction "1_1") (pintype "passive"))
      (node (ref "R5") (pin "2") (pinfunction "2_2") (pintype "passive"))
      (node (ref "U1") (pin "4") (pinfunction "FB_4") (pintype "passive"))
    )
    (net (code "34") (name "/FB2") (class "Default")
      (node (ref "R50") (pin "2") (pinfunction "2_2") (pintype "passive"))
      (node (ref "R51") (pin "1") (pinfunction "1_1") (pintype "passive"))
      (node (ref "U6") (pin "4") (pinfunction "FB_4") (pintype "passive"))
    )
    (net (code "35") (name "/FB3") (class "Default")
      (node (ref "R56") (pin "1") (pinfunction "1_1") (pintype "passive"))
      (node (ref "R6") (pin "2") (pinfunction "2_2") (pintype "passive"))
      (node (ref "U13") (pin "4") (pinfunction "FB_4") (pintype "passive"))
    )
    (net (code "36") (name "/GPIO0") (class "Default")
      (node (ref "B1") (pin "27") (pinfunction "GPIO0_27") (pintype "passive"))
      (node (ref "C21") (pin "1") (pinfunction "1_1") (pintype "passive"))
      (node (ref "R19") (pin "1") (pinfunction "1_1") (pintype "passive"))
      (node (ref "SW2") (pin "2") (pinfunction "2_2") (pintype "passive"))
      (node (ref "SW2") (pin "3") (pinfunction "3_3") (pintype "passive"))
    )
    (net (code "37") (name "/GPIO11") (class "Default")
      (node (ref "B1") (pin "19") (pinfunction "GPIO11_19") (pintype "passive"))
      (node (ref "JP5") (pin "3") (pinfunction "3_3") (pintype "passive"))
    )
    (net (code "38") (name "/GPIO12") (class "Default")
      (node (ref "B1") (pin "20") (pinfunction "GPIO12_20") (pintype "passive"))
      (node (ref "JP5") (pin "4") (pinfunction "4_4") (pintype "passive"))
    )
    (net (code "39") (name "/GPIO13") (class "Default")
      (node (ref "B1") (pin "21") (pinfunction "GPIO13_21") (pintype "passive"))
      (node (ref "JP5") (pin "5") (pinfunction "5_5") (pintype "passive"))
    )
    (net (code "40") (name "/GPIO14") (class "Default")
      (node (ref "B1") (pin "22") (pinfunction "GPIO14_22") (pintype "passive"))
      (node (ref "JP5") (pin "6") (pinfunction "6_6") (pintype "passive"))
    )
    (net (code "41") (name "/HLED") (class "Default")
      (node (ref "RFAST1") (pin "2") (pinfunction "2_2") (pintype "passive"))
      (node (ref "U9") (pin "5") (pinfunction "HLED_5") (pintype "passive"))
    )
    (net (code "42") (name "/LRCK") (class "Default")
      (node (ref "B1") (pin "9") (pinfunction "GPIO16_9") (pintype "passive"))
      (node (ref "U8") (pin "14") (pinfunction "LRCLK_14") (pintype "passive"))
    )
    (net (code "43") (name "/OE") (class "Default")
      (node (ref "B1") (pin "12") (pinfunction "GPIO8_12") (pintype "passive"))
      (node (ref "R31") (pin "2") (pinfunction "2_2") (pintype "passive"))
      (node (ref "U2") (pin "23") (pinfunction "~{OE}_23") (pintype "passive"))
    )
    (net (code "44") (name "/PWM0") (class "Default")
      (node (ref "P1") (pin "1") (pinfunction "1_1") (pintype "passive"))
      (node (ref "R26") (pin "1") (pinfunction "1_1") (pintype "passive"))
    )
    (net (code "45") (name "/PWM1") (class "Default")
      (node (ref "P2") (pin "1") (pinfunction "1_1") (pintype "passive"))
      (node (ref "R28") (pin "2") (pinfunction "2_2") (pintype "passive"))
    )
    (net (code "46") (name "/PWM2") (class "Default")
      (node (ref "P3") (pin "1") (pinfunction "1_1") (pintype "passive"))
      (node (ref "R29") (pin "2") (pinfunction "2_2") (pintype "passive"))
    )
    (net (code "47") (name "/PWM3") (class "Default")
      (node (ref "P4") (pin "1") (pinfunction "1_1") (pintype "passive"))
      (node (ref "R30") (pin "2") (pinfunction "2_2") (pintype "passive"))
    )
    (net (code "48") (name "/PWM4") (class "Default")
      (node (ref "P5") (pin "1") (pinfunction "1_1") (pintype "passive"))
      (node (ref "R32") (pin "2") (pinfunction "2_2") (pintype "passive"))
    )
    (net (code "49") (name "/PWM5") (class "Default")
      (node (ref "P6") (pin "1") (pinfunction "1_1") (pintype "passive"))
      (node (ref "R33") (pin "2") (pinfunction "2_2") (pintype "passive"))
    )
    (net (code "50") (name "/PWM6") (class "Default")
      (node (ref "P7") (pin "1") (pinfunction "1_1") (pintype "passive"))
      (node (ref "R34") (pin "2") (pinfunction "2_2") (pintype "passive"))
    )
    (net (code "51") (name "/PWM7") (class "Default")
      (node (ref "P8") (pin "1") (pinfunction "1_1") (pintype "passive"))
      (node (ref "R35") (pin "2") (pinfunction "2_2") (pintype "passive"))
    )
    (net (code "52") (name "/PWM8") (class "Default")
      (node (ref "P9") (pin "1") (pinfunction "1_1") (pintype "passive"))
      (node (ref "R36") (pin "2") (pinfunction "2_2") (pintype "passive"))
    )
    (net (code "53") (name "/PWM9") (class "Default")
      (node (ref "P10") (pin "1") (pinfunction "1_1") (pintype "passive"))
      (node (ref "R37") (pin "2") (pinfunction "2_2") (pintype "passive"))
    )
    (net (code "54") (name "/PWM10") (class "Default")
      (node (ref "P11") (pin "1") (pinfunction "1_1") (pintype "passive"))
      (node (ref "R38") (pin "2") (pinfunction "2_2") (pintype "passive"))
    )
    (net (code "55") (name "/PWM11") (class "Default")
      (node (ref "P12") (pin "1") (pinfunction "1_1") (pintype "passive"))
      (node (ref "R39") (pin "2") (pinfunction "2_2") (pintype "passive"))
    )
    (net (code "56") (name "/PWM12") (class "Default")
      (node (ref "P13") (pin "1") (pinfunction "1_1") (pintype "passive"))
      (node (ref "R40") (pin "2") (pinfunction "2_2") (pintype "passive"))
    )
    (net (code "57") (name "/PWM13") (class "Default")
      (node (ref "P14") (pin "1") (pinfunction "1_1") (pintype "passive"))
      (node (ref "R41") (pin "2") (pinfunction "2_2") (pintype "passive"))
    )
    (net (code "58") (name "/PWM14") (class "Default")
      (node (ref "P15") (pin "1") (pinfunction "1_1") (pintype "passive"))
      (node (ref "R42") (pin "2") (pinfunction "2_2") (pintype "passive"))
    )
    (net (code "59") (name "/PWM15") (class "Default")
      (node (ref "P16") (pin "1") (pinfunction "1_1") (pintype "passive"))
      (node (ref "R46") (pin "2") (pinfunction "2_2") (pintype "passive"))
    )
    (net (code "60") (name "/P_EN") (class "Default")
      (node (ref "C13") (pin "2") (pinfunction "2_2") (pintype "passive"))
      (node (ref "R17") (pin "2") (pinfunction "2_2") (pintype "passive"))
      (node (ref "R22") (pin "1") (pinfunction "1_1") (pintype "passive"))
      (node (ref "R23") (pin "2") (pinfunction "2_2") (pintype "passive"))
    )
    (net (code "61") (name "/P_EN1") (class "Default")
      (node (ref "R23") (pin "1") (pinfunction "1_1") (pintype "passive"))
      (node (ref "U1") (pin "5") (pinfunction "EN_5") (pintype "passive"))
    )
    (net (code "62") (name "/RXD0") (class "Default")
      (node (ref "B1") (pin "36") (pinfunction "RXD0_36") (pintype "passive"))
      (node (ref "LED3") (pin "2") (pinfunction "K_2") (pintype "passive"))
      (node (ref "R13") (pin "1") (pinfunction "1_1") (pintype "passive"))
    )
    (net (code "63") (name "/RXD1") (class "Default")
      (node (ref "B1") (pin "18") (pinfunction "GPIO10_18") (pintype "passive"))
      (node (ref "JP5") (pin "2") (pinfunction "2_2") (pintype "passive"))
    )
    (net (code "64") (name "/SCK") (class "Default")
      (node (ref "B1") (pin "5") (pinfunction "GPIO5_5") (pintype "passive"))
      (node (ref "U7") (pin "1") (pinfunction "SCK_1") (pintype "passive"))
    )
    (net (code "65") (name "/SCL") (class "Default")
      (node (ref "B1") (pin "11") (pinfunction "GPIO18_11") (pintype "passive"))
      (node (ref "R27") (pin "1") (pinfunction "1_1") (pintype "passive"))
      (node (ref "U2") (pin "26") (pinfunction "SCL_26") (pintype "passive"))
    )
    (net (code "66") (name "/SD") (class "Default")
      (node (ref "B1") (pin "6") (pinfunction "GPIO6_6") (pintype "passive"))
      (node (ref "R52") (pin "2") (pinfunction "2_2") (pintype "passive"))
      (node (ref "U7") (pin "2") (pinfunction "SD_2") (pintype "passive"))
    )
    (net (code "67") (name "/SDA") (class "Default")
      (node (ref "B1") (pin "10") (pinfunction "GPIO17_10") (pintype "passive"))
      (node (ref "R25") (pin "1") (pinfunction "1_1") (pintype "passive"))
      (node (ref "U2") (pin "27") (pinfunction "SDA_27") (pintype "passive"))
    )
    (net (code "68") (name "/SD_MODF") (class "Default")
      (node (ref "R53") (pin "2") (pinfunction "2_2") (pintype "passive"))
      (node (ref "U8") (pin "4") (pinfunction "~{SD_MODE}_4") (pintype "passive"))
    )
    (net (code "69") (name "/TXD0") (class "Default")
      (node (ref "B1") (pin "37") (pinfunction "TXD0_37") (pintype "passive"))
      (node (ref "LED2") (pin "2") (pinfunction "K_2") (pintype "passive"))
      (node (ref "R15") (pin "1") (pinfunction "1_1") (pintype "passive"))
    )
    (net (code "70") (name "/TXD1") (class "Default")
      (node (ref "B1") (pin "17") (pinfunction "GPIO9_17") (pintype "passive"))
      (node (ref "JP5") (pin "1") (pinfunction "1_1") (pintype "passive"))
    )
    (net (code "71") (name "/USB_D+") (class "Default")
      (node (ref "TYPE-C1") (pin "A6") (pinfunction "DP1_A6") (pintype "passive"))
      (node (ref "TYPE-C1") (pin "B6") (pinfunction "DP2_B6") (pintype "passive"))
      (node (ref "U3") (pin "5") (pinfunction "D+_5") (pintype "passive"))
    )
    (net (code "72") (name "/USB_D-") (class "Default")
      (node (ref "TYPE-C1") (pin "A7") (pinfunction "DN1_A7") (pintype "passive"))
      (node (ref "TYPE-C1") (pin "B7") (pinfunction "DN2_B7") (pintype "passive"))
      (node (ref "U3") (pin "6") (pinfunction "D-_6") (pintype "passive"))
    )
    (net (code "73") (name "/VBUSL_CIO1") (class "Default")
      (node (ref "C33") (pin "1") (pinfunction "1_1") (pintype "passive"))
      (node (ref "TYPE-C2") (pin "A4B9") (pinfunction "VBUS_A4B9") (pintype "passive"))
      (node (ref "TYPE-C2") (pin "B4A9") (pinfunction "VBUS_B4A9") (pintype "passive"))
      (node (ref "U10") (pin "1") (pinfunction "S_1") (pintype "passive"))
      (node (ref "U10") (pin "2") (pinfunction "S_2") (pintype "passive"))
      (node (ref "U10") (pin "3") (pinfunction "S_3") (pintype "passive"))
      (node (ref "U9") (pin "8") (pinfunction "VBUS_8") (pintype "passive"))
    )
    (net (code "74") (name "/VBUSL_Source") (class "Default")
      (node (ref "CL1") (pin "1") (pinfunction "A_1") (pintype "passive"))
      (node (ref "CL2") (pin "2") (pinfunction "2_2") (pintype "passive"))
      (node (ref "CL3") (pin "2") (pinfunction "2_2") (pintype "passive"))
      (node (ref "CL4") (pin "2") (pinfunction "2_2") (pintype "passive"))
      (node (ref "CSC1") (pin "1") (pinfunction "1_1") (pintype "passive"))
      (node (ref "RSCL1") (pin "2") (pinfunction "2_2") (pintype "passive"))
      (node (ref "U10") (pin "5") (pinfunction "D_5") (pintype "passive"))
      (node (ref "U10") (pin "6") (pinfunction "D_6") (pintype "passive"))
      (node (ref "U10") (pin "7") (pinfunction "D_7") (pintype "passive"))
      (node (ref "U10") (pin "8") (pinfunction "D_8") (pintype "passive"))
      (node (ref "U10") (pin "9") (pinfunction "D_9") (pintype "passive"))
      (node (ref "U9") (pin "10") (pinfunction "VBUSI_10") (pintype "passive"))
      (node (ref "U9") (pin "12") (pinfunction "VIO_12") (pintype "passive"))
      (node (ref "U9") (pin "13") (pinfunction "CSP1_13") (pintype "passive"))
    )
    (net (code "75") (name "/VD+") (class "Default")
      (node (ref "C30") (pin "2") (pinfunction "2_2") (pintype "passive"))
      (node (ref "FB1") (pin "2") (pintype "passive"))
      (node (ref "P17") (pin "2") (pinfunction "2_2") (pintype "passive"))
    )
    (net (code "76") (name "/VD-") (class "Default")
      (node (ref "C29") (pin "2") (pinfunction "2_2") (pintype "passive"))
      (node (ref "FB2") (pin "2") (pintype "passive"))
      (node (ref "P17") (pin "1") (pinfunction "1_1") (pintype "passive"))
    )
    (net (code "77") (name "/VIN") (class "Default")
      (node (ref "C22") (pin "1") (pinfunction "1_1") (pintype "passive"))
      (node (ref "C23") (pin "2") (pinfunction "2_2") (pintype "passive"))
      (node (ref "C24") (pin "2") (pinfunction "2_2") (pintype "passive"))
      (node (ref "C25") (pin "2") (pinfunction "2_2") (pintype "passive"))
      (node (ref "C34") (pin "2") (pinfunction "2_2") (pintype "passive"))
      (node (ref "C35") (pin "2") (pinfunction "2_2") (pintype "passive"))
      (node (ref "C36") (pin "2") (pinfunction "2_2") (pintype "passive"))
      (node (ref "C5") (pin "2") (pinfunction "2_2") (pintype "passive"))
      (node (ref "C6") (pin "2") (pinfunction "2_2") (pintype "passive"))
      (node (ref "C7") (pin "2") (pinfunction "2_2") (pintype "passive"))
      (node (ref "CE1") (pin "1") (pinfunction "A_1") (pintype "passive"))
      (node (ref "CE2") (pin "1") (pinfunction "A_1") (pintype "passive"))
      (node (ref "JP4") (pin "1") (pinfunction "1_1") (pintype "passive"))
      (node (ref "KY1") (pin "1") (pinfunction "1_1") (pintype "passive"))
      (node (ref "R17") (pin "1") (pinfunction "1_1") (pintype "passive"))
      (node (ref "R2") (pin "2") (pinfunction "2_2") (pintype "passive"))
      (node (ref "U1") (pin "7") (pinfunction "VIN_7") (pintype "passive"))
      (node (ref "U13") (pin "7") (pinfunction "VIN_7") (pintype "passive"))
      (node (ref "U4") (pin "5") (pinfunction "VM_5") (pintype "passive"))
      (node (ref "U5") (pin "5") (pinfunction "VM_5") (pintype "passive"))
      (node (ref "U6") (pin "7") (pinfunction "VIN_7") (pintype "passive"))
    )
    (net (code "78") (name "/VIN_SW") (class "Default")
      (node (ref "CR1") (pin "2") (pinfunction "2_2") (pintype "passive"))
      (node (ref "CR2") (pin "2") (pinfunction "2_2") (pintype "passive"))
      (node (ref "CR3") (pin "2") (pinfunction "2_2") (pintype "passive"))
      (node (ref "CR4") (pin "1") (pinfunction "A_1") (pintype "passive"))
      (node (ref "CSC2") (pin "2") (pinfunction "2_2") (pintype "passive"))
      (node (ref "JP1") (pin "1") (pinfunction "1_1") (pintype "passive"))
      (node (ref "KY1") (pin "2") (pinfunction "2_2") (pintype "passive"))
      (node (ref "RSCR1") (pin "2") (pinfunction "2_2") (pintype "passive"))
      (node (ref "U9") (pin "26") (pinfunction "CSP2_26") (pintype "passive"))
      (node (ref "U9") (pin "27") (pinfunction "BAT_27") (pintype "passive"))
      (node (ref "XT60电池接口") (pin "1") (pinfunction "1_1") (pintype "passive"))
    )
    (net (code "79") (name "/WS") (class "Default")
      (node (ref "B1") (pin "4") (pinfunction "GPIO4_4") (pintype "passive"))
      (node (ref "U7") (pin "3") (pinfunction "WS_3") (pintype "passive"))
    )
    (net (code "80") (name "3.3V") (class "Default")
      (node (ref "B1") (pin "2") (pinfunction "3V3_2") (pintype "passive"))
      (node (ref "C1") (pin "2") (pinfunction "2_2") (pintype "passive"))
      (node (ref "C15") (pin "2") (pinfunction "2_2") (pintype "passive"))
      (node (ref "C2") (pin "2") (pinfunction "2_2") (pintype "passive"))
      (node (ref "C31") (pin "2") (pinfunction "2_2") (pintype "passive"))
      (node (ref "C32") (pin "2") (pinfunction "2_2") (pintype "passive"))
      (node (ref "C8") (pin "1") (pinfunction "1_1") (pintype "passive"))
      (node (ref "C9") (pin "1") (pinfunction "1_1") (pintype "passive"))
      (node (ref "D4") (pin "1") (pinfunction "A_1") (pintype "passive"))
      (node (ref "R21") (pin "2") (pinfunction "2_2") (pintype "passive"))
      (node (ref "R25") (pin "2") (pinfunction "2_2") (pintype "passive"))
      (node (ref "R27") (pin "2") (pinfunction "2_2") (pintype "passive"))
      (node (ref "R53") (pin "1") (pinfunction "1_1") (pintype "passive"))
      (node (ref "R7") (pin "2") (pinfunction "2_2") (pintype "passive"))
      (node (ref "R8") (pin "2") (pinfunction "2_2") (pintype "passive"))
      (node (ref "R9") (pin "2") (pinfunction "2_2") (pintype "passive"))
      (node (ref "U2") (pin "28") (pinfunction "VDD_28") (pintype "passive"))
      (node (ref "U4") (pin "4") (pinfunction "VREF_4") (pintype "passive"))
      (node (ref "U5") (pin "4") (pinfunction "VREF_4") (pintype "passive"))
      (node (ref "U7") (pin "7") (pinfunction "VDD_7") (pintype "passive"))
      (node (ref "U7") (pin "8") (pinfunction "CHIPEN_8") (pintype "passive"))
      (node (ref "U8") (pin "7") (pinfunction "VDD_7") (pintype "passive"))
      (node (ref "U8") (pin "8") (pinfunction "VDD_8") (pintype "passive"))
      (node (ref "V1") (pin "2") (pinfunction "Vout_2") (pintype "passive"))
      (node (ref "W1") (pin "1") (pinfunction "1_1") (pintype "passive"))
      (node (ref "W2") (pin "1") (pinfunction "1_1") (pintype "passive"))
      (node (ref "W3") (pin "1") (pinfunction "1_1") (pintype "passive"))
      (node (ref "W4") (pin "1") (pinfunction "1_1") (pintype "passive"))
      (node (ref "W5") (pin "1") (pinfunction "1_1") (pintype "passive"))
      (node (ref "W6") (pin "1") (pinfunction "1_1") (pintype "passive"))
    )
    (net (code "81") (name "5V") (class "Default")
      (node (ref "C11") (pin "1") (pinfunction "1_1") (pintype "passive"))
      (node (ref "C12") (pin "1") (pinfunction "1_1") (pintype "passive"))
      (node (ref "C14") (pin "2") (pinfunction "2_2") (pintype "passive"))
      (node (ref "C19") (pin "2") (pinfunction "2_2") (pintype "passive"))
      (node (ref "C20") (pin "2") (pinfunction "2_2") (pintype "passive"))
      (node (ref "C3") (pin "2") (pinfunction "2_2") (pintype "passive"))
      (node (ref "C4") (pin "2") (pinfunction "2_2") (pintype "passive"))
      (node (ref "D1") (pin "2") (pinfunction "K_2") (pintype "passive"))
      (node (ref "JP2") (pin "5") (pinfunction "5_5") (pintype "passive"))
      (node (ref "JP3") (pin "5") (pinfunction "5_5") (pintype "passive"))
      (node (ref "L1") (pin "1") (pinfunction "1_1") (pintype "passive"))
      (node (ref "R5") (pin "1") (pinfunction "1_1") (pintype "passive"))
      (node (ref "U3") (pin "16") (pinfunction "VCC_16") (pintype "passive"))
      (node (ref "V1") (pin "3") (pinfunction "Vin_3") (pintype "passive"))
    )
    (net (code "82") (name "5V树莓派") (class "Default")
      (node (ref "C38") (pin "1") (pinfunction "1_1") (pintype "passive"))
      (node (ref "C39") (pin "1") (pinfunction "1_1") (pintype "passive"))
      (node (ref "L4") (pin "1") (pinfunction "1_1") (pintype "passive"))
      (node (ref "R57") (pin "2") (pinfunction "2_2") (pintype "passive"))
      (node (ref "R6") (pin "1") (pinfunction "1_1") (pintype "passive"))
      (node (ref "TYPE-C3") (pin "A4B9") (pinfunction "VBUS_A4B9") (pintype "passive"))
      (node (ref "TYPE-C3") (pin "B4A9") (pinfunction "VBUS_B4A9") (pintype "passive"))
    )
    (net (code "83") (name "GND") (class "Default")
      (node (ref "B1") (pin "1") (pinfunction "GND_1") (pintype "passive"))
      (node (ref "B1") (pin "40") (pinfunction "GND_40") (pintype "passive"))
      (node (ref "B1") (pin "41") (pinfunction "EP_41") (pintype "passive"))
      (node (ref "BAT-MODE1") (pin "2") (pinfunction "2_2") (pintype "passive"))
      (node (ref "C1") (pin "1") (pinfunction "1_1") (pintype "passive"))
      (node (ref "C11") (pin "2") (pinfunction "2_2") (pintype "passive"))
      (node (ref "C12") (pin "2") (pinfunction "2_2") (pintype "passive"))
      (node (ref "C13") (pin "1") (pinfunction "1_1") (pintype "passive"))
      (node (ref "C14") (pin "1") (pinfunction "1_1") (pintype "passive"))
      (node (ref "C15") (pin "1") (pinfunction "1_1") (pintype "passive"))
      (node (ref "C16") (pin "1") (pinfunction "1_1") (pintype "passive"))
      (node (ref "C17") (pin "2") (pinfunction "2_2") (pintype "passive"))
      (node (ref "C18") (pin "2") (pinfunction "2_2") (pintype "passive"))
      (node (ref "C19") (pin "1") (pinfunction "1_1") (pintype "passive"))
      (node (ref "C2") (pin "1") (pinfunction "1_1") (pintype "passive"))
      (node (ref "C20") (pin "1") (pinfunction "1_1") (pintype "passive"))
      (node (ref "C21") (pin "2") (pinfunction "2_2") (pintype "passive"))
      (node (ref "C22") (pin "2") (pinfunction "2_2") (pintype "passive"))
      (node (ref "C23") (pin "1") (pinfunction "1_1") (pintype "passive"))
      (node (ref "C24") (pin "1") (pinfunction "1_1") (pintype "passive"))
      (node (ref "C25") (pin "1") (pinfunction "1_1") (pintype "passive"))
      (node (ref "C27") (pin "2") (pinfunction "2_2") (pintype "passive"))
      (node (ref "C28") (pin "2") (pinfunction "2_2") (pintype "passive"))
      (node (ref "C29") (pin "1") (pinfunction "1_1") (pintype "passive"))
      (node (ref "C3") (pin "1") (pinfunction "1_1") (pintype "passive"))
      (node (ref "C30") (pin "1") (pinfunction "1_1") (pintype "passive"))
      (node (ref "C31") (pin "1") (pinfunction "1_1") (pintype "passive"))
      (node (ref "C32") (pin "1") (pinfunction "1_1") (pintype "passive"))
      (node (ref "C33") (pin "2") (pinfunction "2_2") (pintype "passive"))
      (node (ref "C34") (pin "1") (pinfunction "1_1") (pintype "passive"))
      (node (ref "C35") (pin "1") (pinfunction "1_1") (pintype "passive"))
      (node (ref "C36") (pin "1") (pinfunction "1_1") (pintype "passive"))
      (node (ref "C38") (pin "2") (pinfunction "2_2") (pintype "passive"))
      (node (ref "C39") (pin "2") (pinfunction "2_2") (pintype "passive"))
      (node (ref "C4") (pin "1") (pinfunction "1_1") (pintype "passive"))
      (node (ref "C40") (pin "1") (pinfunction "1_1") (pintype "passive"))
      (node (ref "C5") (pin "1") (pinfunction "1_1") (pintype "passive"))
      (node (ref "C6") (pin "1") (pinfunction "1_1") (pintype "passive"))
      (node (ref "C7") (pin "1") (pinfunction "1_1") (pintype "passive"))
      (node (ref "C8") (pin "2") (pinfunction "2_2") (pintype "passive"))
      (node (ref "C9") (pin "2") (pinfunction "2_2") (pintype "passive"))
      (node (ref "CC1") (pin "1") (pinfunction "1_1") (pintype "passive"))
      (node (ref "CC2") (pin "1") (pinfunction "1_1") (pintype "passive"))
      (node (ref "CE1") (pin "2") (pinfunction "K_2") (pintype "passive"))
      (node (ref "CE2") (pin "2") (pinfunction "K_2") (pintype "passive"))
      (node (ref "CL1") (pin "2") (pinfunction "K_2") (pintype "passive"))
      (node (ref "CL2") (pin "1") (pinfunction "1_1") (pintype "passive"))
      (node (ref "CL3") (pin "1") (pinfunction "1_1") (pintype "passive"))
      (node (ref "CL4") (pin "1") (pinfunction "1_1") (pintype "passive"))
      (node (ref "CNTC") (pin "2") (pinfunction "2_2") (pintype "passive"))
      (node (ref "CR1") (pin "1") (pinfunction "1_1") (pintype "passive"))
      (node (ref "CR2") (pin "1") (pinfunction "1_1") (pintype "passive"))
      (node (ref "CR3") (pin "1") (pinfunction "1_1") (pintype "passive"))
      (node (ref "CR4") (pin "2") (pinfunction "K_2") (pintype "passive"))
      (node (ref "CVC1") (pin "2") (pinfunction "2_2") (pintype "passive"))
      (node (ref "CVC2") (pin "2") (pinfunction "2_2") (pintype "passive"))
      (node (ref "D10") (pin "1") (pinfunction "A_1") (pintype "passive"))
      (node (ref "D11") (pin "1") (pinfunction "A_1") (pintype "passive"))
      (node (ref "D2") (pin "1") (pinfunction "A_1") (pintype "passive"))
      (node (ref "D3") (pin "1") (pinfunction "A_1") (pintype "passive"))
      (node (ref "D5") (pin "1") (pinfunction "A_1") (pintype "passive"))
      (node (ref "FAST1") (pin "2") (pinfunction "K_2") (pintype "passive"))
      (node (ref "ISET-MODE1") (pin "2") (pinfunction "2_2") (pintype "passive"))
      (node (ref "JP1") (pin "2") (pinfunction "2_2") (pintype "passive"))
      (node (ref "JP2") (pin "2") (pinfunction "2_2") (pintype "passive"))
      (node (ref "JP3") (pin "2") (pinfunction "2_2") (pintype "passive"))
      (node (ref "JP4") (pin "2") (pinfunction "2_2") (pintype "passive"))
      (node (ref "LED1") (pin "2") (pinfunction "K_2") (pintype "passive"))
      (node (ref "P1") (pin "3") (pinfunction "3_3") (pintype "passive"))
      (node (ref "P10") (pin "3") (pinfunction "3_3") (pintype "passive"))
      (node (ref "P11") (pin "3") (pinfunction "3_3") (pintype "passive"))
      (node (ref "P12") (pin "3") (pinfunction "3_3") (pintype "passive"))
      (node (ref "P13") (pin "3") (pinfunction "3_3") (pintype "passive"))
      (node (ref "P14") (pin "3") (pinfunction "3_3") (pintype "passive"))
      (node (ref "P15") (pin "3") (pinfunction "3_3") (pintype "passive"))
      (node (ref "P16") (pin "3") (pinfunction "3_3") (pintype "passive"))
      (node (ref "P2") (pin "3") (pinfunction "3_3") (pintype "passive"))
      (node (ref "P3") (pin "3") (pinfunction "3_3") (pintype "passive"))
      (node (ref "P4") (pin "3") (pinfunction "3_3") (pintype "passive"))
      (node (ref "P5") (pin "3") (pinfunction "3_3") (pintype "passive"))
      (node (ref "P6") (pin "3") (pinfunction "3_3") (pintype "passive"))
      (node (ref "P7") (pin "3") (pinfunction "3_3") (pintype "passive"))
      (node (ref "P8") (pin "3") (pinfunction "3_3") (pintype "passive"))
      (node (ref "P9") (pin "3") (pinfunction "3_3") (pintype "passive"))
      (node (ref "R1") (pin "1") (pinfunction "1_1") (pintype "passive"))
      (node (ref "R10") (pin "2") (pinfunction "2_2") (pintype "passive"))
      (node (ref "R11") (pin "1") (pinfunction "1_1") (pintype "passive"))
      (node (ref "R14") (pin "2") (pinfunction "2_2") (pintype "passive"))
      (node (ref "R20") (pin "2") (pinfunction "2_2") (pintype "passive"))
      (node (ref "R22") (pin "2") (pinfunction "2_2") (pintype "passive"))
      (node (ref "R24") (pin "2") (pinfunction "2_2") (pintype "passive"))
      (node (ref "R3") (pin "2") (pinfunction "2_2") (pintype "passive"))
      (node (ref "R31") (pin "1") (pinfunction "1_1") (pintype "passive"))
      (node (ref "R4") (pin "1") (pinfunction "1_1") (pintype "passive"))
      (node (ref "R43") (pin "1") (pinfunction "1_1") (pintype "passive"))
      (node (ref "R44") (pin "1") (pinfunction "1_1") (pintype "passive"))
      (node (ref "R45") (pin "1") (pinfunction "1_1") (pintype "passive"))
      (node (ref "R47") (pin "1") (pinfunction "1_1") (pintype "passive"))
      (node (ref "R48") (pin "1") (pinfunction "1_1") (pintype "passive"))
      (node (ref "R49") (pin "1") (pinfunction "1_1") (pintype "passive"))
      (node (ref "R51") (pin "2") (pinfunction "2_2") (pintype "passive"))
      (node (ref "R52") (pin "1") (pinfunction "1_1") (pintype "passive"))
      (node (ref "R54") (pin "1") (pinfunction "1_1") (pintype "passive"))
      (node (ref "R55") (pin "1") (pinfunction "1_1") (pintype "passive"))
      (node (ref "R56") (pin "2") (pinfunction "2_2") (pintype "passive"))
      (node (ref "RBAT") (pin "2") (pinfunction "2_2") (pintype "passive"))
      (node (ref "RCAPS1") (pin "2") (pinfunction "2_2") (pintype "passive"))
      (node (ref "RIS1") (pin "2") (pinfunction "2_2") (pintype "passive"))
      (node (ref "RNTC") (pin "2") (pinfunction "2_2") (pintype "passive"))
      (node (ref "RVS1") (pin "2") (pinfunction "2_2") (pintype "passive"))
      (node (ref "SW1") (pin "1") (pinfunction "1_1") (pintype "passive"))
      (node (ref "SW1") (pin "4") (pinfunction "4_4") (pintype "passive"))
      (node (ref "SW2") (pin "1") (pinfunction "1_1") (pintype "passive"))
      (node (ref "SW2") (pin "4") (pinfunction "4_4") (pintype "passive"))
      (node (ref "TYPE-C1") (pin "0") (pinfunction "SH_0") (pintype "passive"))
      (node (ref "TYPE-C1") (pin "1") (pinfunction "SH_1") (pintype "passive"))
      (node (ref "TYPE-C1") (pin "2") (pinfunction "SH_2") (pintype "passive"))
      (node (ref "TYPE-C1") (pin "3") (pinfunction "SH_3") (pintype "passive"))
      (node (ref "TYPE-C1") (pin "A1B12") (pinfunction "GND_A1B12") (pintype "passive"))
      (node (ref "TYPE-C1") (pin "B1A12") (pinfunction "GND_B1A12") (pintype "passive"))
      (node (ref "TYPE-C2") (pin "0") (pinfunction "SH_0") (pintype "passive"))
      (node (ref "TYPE-C2") (pin "1") (pinfunction "SH_1") (pintype "passive"))
      (node (ref "TYPE-C2") (pin "2") (pinfunction "SH_2") (pintype "passive"))
      (node (ref "TYPE-C2") (pin "3") (pinfunction "SH_3") (pintype "passive"))
      (node (ref "TYPE-C2") (pin "A1B12") (pinfunction "GND_A1B12") (pintype "passive"))
      (node (ref "TYPE-C2") (pin "B1A12") (pinfunction "GND_B1A12") (pintype "passive"))
      (node (ref "TYPE-C3") (pin "0") (pinfunction "SH_0") (pintype "passive"))
      (node (ref "TYPE-C3") (pin "1") (pinfunction "SH_1") (pintype "passive"))
      (node (ref "TYPE-C3") (pin "2") (pinfunction "SH_2") (pintype "passive"))
      (node (ref "TYPE-C3") (pin "3") (pinfunction "SH_3") (pintype "passive"))
      (node (ref "TYPE-C3") (pin "A1B12") (pinfunction "GND_A1B12") (pintype "passive"))
      (node (ref "TYPE-C3") (pin "B1A12") (pinfunction "GND_B1A12") (pintype "passive"))
      (node (ref "U1") (pin "6") (pinfunction "GND_6") (pintype "passive"))
      (node (ref "U1") (pin "9") (pinfunction "PAD_9") (pintype "passive"))
      (node (ref "U13") (pin "6") (pinfunction "GND_6") (pintype "passive"))
      (node (ref "U13") (pin "9") (pinfunction "PAD_9") (pintype "passive"))
      (node (ref "U14") (pin "1") (pinfunction "S_1") (pintype "passive"))
      (node (ref "U14") (pin "2") (pinfunction "S_2") (pintype "passive"))
      (node (ref "U14") (pin "3") (pinfunction "S_3") (pintype "passive"))
      (node (ref "U15") (pin "1") (pinfunction "S_1") (pintype "passive"))
      (node (ref "U15") (pin "2") (pinfunction "S_2") (pintype "passive"))
      (node (ref "U15") (pin "3") (pinfunction "S_3") (pintype "passive"))
      (node (ref "U16") (pin "2") (pinfunction "GND_2") (pintype "passive"))
      (node (ref "U2") (pin "14") (pinfunction "GND_14") (pintype "passive"))
      (node (ref "U2") (pin "25") (pinfunction "EXTCLK_25") (pintype "passive"))
      (node (ref "U3") (pin "1") (pinfunction "GND_1") (pintype "passive"))
      (node (ref "U4") (pin "1") (pinfunction "GND_1") (pintype "passive"))
      (node (ref "U4") (pin "9") (pinfunction "EP_9") (pintype "passive"))
      (node (ref "U5") (pin "1") (pinfunction "GND_1") (pintype "passive"))
      (node (ref "U5") (pin "9") (pinfunction "EP_9") (pintype "passive"))
      (node (ref "U6") (pin "6") (pinfunction "GND_6") (pintype "passive"))
      (node (ref "U6") (pin "9") (pinfunction "PAD_9") (pintype "passive"))
      (node (ref "U7") (pin "4") (pinfunction "L/R_4") (pintype "passive"))
      (node (ref "U7") (pin "5") (pinfunction "GND_5") (pintype "passive"))
      (node (ref "U7") (pin "6") (pinfunction "GND_6") (pintype "passive"))
      (node (ref "U7") (pin "9") (pinfunction "GND_9") (pintype "passive"))
      (node (ref "U8") (pin "11") (pinfunction "GND_11") (pintype "passive"))
      (node (ref "U8") (pin "15") (pinfunction "GND_15") (pintype "passive"))
      (node (ref "U8") (pin "17") (pinfunction "GND_17") (pintype "passive"))
      (node (ref "U8") (pin "3") (pinfunction "GND_3") (pintype "passive"))
      (node (ref "U9") (pin "11") (pinfunction "AGND_11") (pintype "passive"))
      (node (ref "U9") (pin "30") (pinfunction "AGND_30") (pintype "passive"))
      (node (ref "U9") (pin "49") (pinfunction "EP_49") (pintype "passive"))
      (node (ref "V1") (pin "1") (pinfunction "GND_1") (pintype "passive"))
      (node (ref "XT60电池接口") (pin "2") (pinfunction "2_2") (pintype "passive"))
    )
    (net (code "84") (name "Net-(CC1-Pad2)") (class "Default")
      (node (ref "CC1") (pin "2") (pinfunction "2_2") (pintype "passive"))
      (node (ref "RC1") (pin "2") (pinfunction "2_2") (pintype "passive"))
    )
    (net (code "85") (name "Net-(CC2-Pad2)") (class "Default")
      (node (ref "CC2") (pin "2") (pinfunction "2_2") (pintype "passive"))
      (node (ref "RC2") (pin "2") (pinfunction "2_2") (pintype "passive"))
    )
    (net (code "86") (name "Net-(D2-K)") (class "Default")
      (node (ref "C37") (pin "1") (pinfunction "1_1") (pintype "passive"))
      (node (ref "D2") (pin "2") (pinfunction "K_2") (pintype "passive"))
      (node (ref "L4") (pin "2") (pinfunction "2_2") (pintype "passive"))
      (node (ref "U13") (pin "8") (pinfunction "SW_8") (pintype "passive"))
    )
    (net (code "87") (name "Net-(D3-K)") (class "Default")
      (node (ref "C10") (pin "1") (pinfunction "1_1") (pintype "passive"))
      (node (ref "D3") (pin "2") (pinfunction "K_2") (pintype "passive"))
      (node (ref "L1") (pin "2") (pinfunction "2_2") (pintype "passive"))
      (node (ref "U1") (pin "8") (pinfunction "SW_8") (pintype "passive"))
    )
    (net (code "88") (name "Net-(D4-K)") (class "Default")
      (node (ref "D4") (pin "2") (pinfunction "K_2") (pintype "passive"))
      (node (ref "R24") (pin "1") (pinfunction "1_1") (pintype "passive"))
    )
    (net (code "89") (name "Net-(D5-K)") (class "Default")
      (node (ref "C26") (pin "1") (pinfunction "1_1") (pintype "passive"))
      (node (ref "D5") (pin "2") (pinfunction "K_2") (pintype "passive"))
      (node (ref "L2") (pin "2") (pinfunction "2_2") (pintype "passive"))
      (node (ref "U6") (pin "8") (pinfunction "SW_8") (pintype "passive"))
    )
    (net (code "90") (name "Net-(D6-A)") (class "Default")
      (node (ref "D6") (pin "1") (pinfunction "A_1") (pintype "passive"))
      (node (ref "D7") (pin "2") (pinfunction "K_2") (pintype "passive"))
      (node (ref "RLED1") (pin "2") (pinfunction "2_2") (pintype "passive"))
    )
    (net (code "91") (name "Net-(D6-K)") (class "Default")
      (node (ref "D6") (pin "2") (pinfunction "K_2") (pintype "passive"))
      (node (ref "D7") (pin "1") (pinfunction "A_1") (pintype "passive"))
      (node (ref "D8") (pin "2") (pinfunction "K_2") (pintype "passive"))
      (node (ref "D9") (pin "1") (pinfunction "A_1") (pintype "passive"))
      (node (ref "R54") (pin "2") (pinfunction "2_2") (pintype "passive"))
      (node (ref "U9") (pin "4") (pinfunction "LED3_4") (pintype "passive"))
    )
    (net (code "92") (name "Net-(D8-A)") (class "Default")
      (node (ref "D8") (pin "1") (pinfunction "A_1") (pintype "passive"))
      (node (ref "D9") (pin "2") (pinfunction "K_2") (pintype "passive"))
      (node (ref "RLED2") (pin "1") (pinfunction "1_1") (pintype "passive"))
    )
    (net (code "93") (name "Net-(D10-K)") (class "Default")
      (node (ref "CBSL1") (pin "2") (pinfunction "2_2") (pintype "passive"))
      (node (ref "D10") (pin "2") (pinfunction "K_2") (pintype "passive"))
      (node (ref "U9") (pin "17") (pinfunction "BST1_17") (pintype "passive"))
    )
    (net (code "94") (name "Net-(D11-K)") (class "Default")
      (node (ref "CBSR1") (pin "1") (pinfunction "1_1") (pintype "passive"))
      (node (ref "D11") (pin "2") (pinfunction "K_2") (pintype "passive"))
      (node (ref "U9") (pin "22") (pinfunction "BST2_22") (pintype "passive"))
    )
    (net (code "95") (name "Net-(FAST1-A)") (class "Default")
      (node (ref "FAST1") (pin "1") (pinfunction "A_1") (pintype "passive"))
      (node (ref "RFAST1") (pin "1") (pinfunction "1_1") (pintype "passive"))
    )
    (net (code "96") (name "Net-(LED1-A)") (class "Default")
      (node (ref "LED1") (pin "1") (pinfunction "A_1") (pintype "passive"))
      (node (ref "R7") (pin "1") (pinfunction "1_1") (pintype "passive"))
    )
    (net (code "97") (name "Net-(LED2-A)") (class "Default")
      (node (ref "LED2") (pin "1") (pinfunction "A_1") (pintype "passive"))
      (node (ref "R8") (pin "1") (pinfunction "1_1") (pintype "passive"))
    )
    (net (code "98") (name "Net-(LED3-A)") (class "Default")
      (node (ref "LED3") (pin "1") (pinfunction "A_1") (pintype "passive"))
      (node (ref "R9") (pin "1") (pinfunction "1_1") (pintype "passive"))
    )
    (net (code "99") (name "Net-(Q1-B)") (class "Default")
      (node (ref "Q1") (pin "1") (pinfunction "B_1") (pintype "passive"))
      (node (ref "R16") (pin "1") (pinfunction "1_1") (pintype "passive"))
    )
    (net (code "100") (name "Net-(Q1-C)") (class "Default")
      (node (ref "Q1") (pin "3") (pinfunction "C_3") (pintype "passive"))
      (node (ref "R12") (pin "2") (pinfunction "2_2") (pintype "passive"))
    )
    (net (code "101") (name "Net-(Q2-B)") (class "Default")
      (node (ref "Q2") (pin "1") (pinfunction "B_1") (pintype "passive"))
      (node (ref "R18") (pin "1") (pinfunction "1_1") (pintype "passive"))
    )
    (net (code "102") (name "Net-(Q2-C)") (class "Default")
      (node (ref "Q2") (pin "3") (pinfunction "C_3") (pintype "passive"))
      (node (ref "R19") (pin "2") (pinfunction "2_2") (pintype "passive"))
    )
    (net (code "103") (name "Net-(TYPE-C1-CC1)") (class "Default")
      (node (ref "R4") (pin "2") (pinfunction "2_2") (pintype "passive"))
      (node (ref "TYPE-C1") (pin "A5") (pinfunction "CC1_A5") (pintype "passive"))
    )
    (net (code "104") (name "Net-(TYPE-C1-CC2)") (class "Default")
      (node (ref "R1") (pin "2") (pinfunction "2_2") (pintype "passive"))
      (node (ref "TYPE-C1") (pin "B5") (pinfunction "CC2_B5") (pintype "passive"))
    )
    (net (code "105") (name "Net-(U1-BOOT)") (class "Default")
      (node (ref "C10") (pin "2") (pinfunction "2_2") (pintype "passive"))
      (node (ref "U1") (pin "1") (pinfunction "BOOT_1") (pintype "passive"))
    )
    (net (code "106") (name "Net-(U2-PWM0)") (class "Default")
      (node (ref "R26") (pin "2") (pinfunction "2_2") (pintype "passive"))
      (node (ref "U2") (pin "6") (pinfunction "PWM0_6") (pintype "passive"))
    )
    (net (code "107") (name "Net-(U2-PWM1)") (class "Default")
      (node (ref "R28") (pin "1") (pinfunction "1_1") (pintype "passive"))
      (node (ref "U2") (pin "7") (pinfunction "PWM1_7") (pintype "passive"))
    )
    (net (code "108") (name "Net-(U2-PWM2)") (class "Default")
      (node (ref "R29") (pin "1") (pinfunction "1_1") (pintype "passive"))
      (node (ref "U2") (pin "8") (pinfunction "PWM2_8") (pintype "passive"))
    )
    (net (code "109") (name "Net-(U2-PWM3)") (class "Default")
      (node (ref "R30") (pin "1") (pinfunction "1_1") (pintype "passive"))
      (node (ref "U2") (pin "9") (pinfunction "PWM3_9") (pintype "passive"))
    )
    (net (code "110") (name "Net-(U2-PWM4)") (class "Default")
      (node (ref "R32") (pin "1") (pinfunction "1_1") (pintype "passive"))
      (node (ref "U2") (pin "10") (pinfunction "PWM4_10") (pintype "passive"))
    )
    (net (code "111") (name "Net-(U2-PWM5)") (class "Default")
      (node (ref "R33") (pin "1") (pinfunction "1_1") (pintype "passive"))
      (node (ref "U2") (pin "11") (pinfunction "PWM5_11") (pintype "passive"))
    )
    (net (code "112") (name "Net-(U2-PWM6)") (class "Default")
      (node (ref "R34") (pin "1") (pinfunction "1_1") (pintype "passive"))
      (node (ref "U2") (pin "12") (pinfunction "PWM6_12") (pintype "passive"))
    )
    (net (code "113") (name "Net-(U2-PWM7)") (class "Default")
      (node (ref "R35") (pin "1") (pinfunction "1_1") (pintype "passive"))
      (node (ref "U2") (pin "13") (pinfunction "PWM7_13") (pintype "passive"))
    )
    (net (code "114") (name "Net-(U2-PWM8)") (class "Default")
      (node (ref "R36") (pin "1") (pinfunction "1_1") (pintype "passive"))
      (node (ref "U2") (pin "15") (pinfunction "PWM8_15") (pintype "passive"))
    )
    (net (code "115") (name "Net-(U2-PWM9)") (class "Default")
      (node (ref "R37") (pin "1") (pinfunction "1_1") (pintype "passive"))
      (node (ref "U2") (pin "16") (pinfunction "PWM9_16") (pintype "passive"))
    )
    (net (code "116") (name "Net-(U2-PWM10)") (class "Default")
      (node (ref "R38") (pin "1") (pinfunction "1_1") (pintype "passive"))
      (node (ref "U2") (pin "17") (pinfunction "PWM10_17") (pintype "passive"))
    )
    (net (code "117") (name "Net-(U2-PWM11)") (class "Default")
      (node (ref "R39") (pin "1") (pinfunction "1_1") (pintype "passive"))
      (node (ref "U2") (pin "18") (pinfunction "PWM11_18") (pintype "passive"))
    )
    (net (code "118") (name "Net-(U2-PWM12)") (class "Default")
      (node (ref "R40") (pin "1") (pinfunction "1_1") (pintype "passive"))
      (node (ref "U2") (pin "19") (pinfunction "PWM12_19") (pintype "passive"))
    )
    (net (code "119") (name "Net-(U2-PWM13)") (class "Default")
      (node (ref "R41") (pin "1") (pinfunction "1_1") (pintype "passive"))
      (node (ref "U2") (pin "20") (pinfunction "PWM13_20") (pintype "passive"))
    )
    (net (code "120") (name "Net-(U2-PWM14)") (class "Default")
      (node (ref "R42") (pin "1") (pinfunction "1_1") (pintype "passive"))
      (node (ref "U2") (pin "21") (pinfunction "PWM14_21") (pintype "passive"))
    )
    (net (code "121") (name "Net-(U2-PWM15)") (class "Default")
      (node (ref "R46") (pin "1") (pinfunction "1_1") (pintype "passive"))
      (node (ref "U2") (pin "22") (pinfunction "PWM15_22") (pintype "passive"))
    )
    (net (code "122") (name "Net-(U3-RXD)") (class "Default")
      (node (ref "R15") (pin "2") (pinfunction "2_2") (pintype "passive"))
      (node (ref "U3") (pin "3") (pinfunction "RXD_3") (pintype "passive"))
    )
    (net (code "123") (name "Net-(U3-TXD)") (class "Default")
      (node (ref "R13") (pin "2") (pinfunction "2_2") (pintype "passive"))
      (node (ref "U3") (pin "2") (pinfunction "TXD_2") (pintype "passive"))
    )
    (net (code "124") (name "Net-(U3-V3)") (class "Default")
      (node (ref "C16") (pin "2") (pinfunction "2_2") (pintype "passive"))
      (node (ref "U3") (pin "4") (pinfunction "V3_4") (pintype "passive"))
    )
    (net (code "125") (name "Net-(U4-ISEN)") (class "Default")
      (node (ref "R14") (pin "1") (pinfunction "1_1") (pintype "passive"))
      (node (ref "U4") (pin "7") (pinfunction "ISEN_7") (pintype "passive"))
    )
    (net (code "126") (name "Net-(U5-ISEN)") (class "Default")
      (node (ref "R20") (pin "1") (pinfunction "1_1") (pintype "passive"))
      (node (ref "U5") (pin "7") (pinfunction "ISEN_7") (pintype "passive"))
    )
    (net (code "127") (name "Net-(U6-BOOT)") (class "Default")
      (node (ref "C26") (pin "2") (pinfunction "2_2") (pintype "passive"))
      (node (ref "U6") (pin "1") (pinfunction "BOOT_1") (pintype "passive"))
    )
    (net (code "128") (name "Net-(U8-OUTN)") (class "Default")
      (node (ref "FB2") (pin "1") (pintype "passive"))
      (node (ref "U8") (pin "10") (pinfunction "OUTN_10") (pintype "passive"))
    )
    (net (code "129") (name "Net-(U8-OUTP)") (class "Default")
      (node (ref "FB1") (pin "1") (pintype "passive"))
      (node (ref "U8") (pin "9") (pinfunction "OUTP_9") (pintype "passive"))
    )
    (net (code "130") (name "Net-(U9-BAT-NUM)") (class "Default")
      (node (ref "RBAT") (pin "1") (pinfunction "1_1") (pintype "passive"))
      (node (ref "U9") (pin "33") (pinfunction "BAT-NUM_33") (pintype "passive"))
    )
    (net (code "131") (name "Net-(U9-CSN1)") (class "Default")
      (node (ref "CSC1") (pin "2") (pinfunction "2_2") (pintype "passive"))
      (node (ref "RSC2") (pin "2") (pinfunction "2_2") (pintype "passive"))
      (node (ref "U9") (pin "14") (pinfunction "CSN1_14") (pintype "passive"))
    )
    (net (code "132") (name "Net-(U9-CSN2)") (class "Default")
      (node (ref "CSC2") (pin "1") (pinfunction "1_1") (pintype "passive"))
      (node (ref "RSC1") (pin "2") (pinfunction "2_2") (pintype "passive"))
      (node (ref "U9") (pin "25") (pinfunction "CSN2_25") (pintype "passive"))
    )
    (net (code "133") (name "Net-(U9-FCAP)") (class "Default")
      (node (ref "RCAPS1") (pin "1") (pinfunction "1_1") (pintype "passive"))
      (node (ref "U9") (pin "34") (pinfunction "FCAP_34") (pintype "passive"))
    )
    (net (code "134") (name "Net-(U9-ISET)") (class "Default")
      (node (ref "RIS1") (pin "1") (pinfunction "1_1") (pintype "passive"))
      (node (ref "U9") (pin "36") (pinfunction "ISET_36") (pintype "passive"))
    )
    (net (code "135") (name "Net-(U9-ISET-MODE)") (class "Default")
      (node (ref "ISET-MODE1") (pin "1") (pinfunction "1_1") (pintype "passive"))
      (node (ref "U9") (pin "47") (pinfunction "ISET-MODE_47") (pintype "passive"))
    )
    (net (code "136") (name "Net-(U9-LED1)") (class "Default")
      (node (ref "RLED1") (pin "1") (pinfunction "1_1") (pintype "passive"))
      (node (ref "U9") (pin "43") (pinfunction "LED1_43") (pintype "passive"))
    )
    (net (code "137") (name "Net-(U9-LED2)") (class "Default")
      (node (ref "RLED2") (pin "2") (pinfunction "2_2") (pintype "passive"))
      (node (ref "U9") (pin "42") (pinfunction "LED2_42") (pintype "passive"))
    )
    (net (code "138") (name "Net-(U9-LX1)") (class "Default")
      (node (ref "CBSL1") (pin "1") (pinfunction "1_1") (pintype "passive"))
      (node (ref "L3") (pin "1") (pinfunction "1_1") (pintype "passive"))
      (node (ref "RC2") (pin "1") (pinfunction "1_1") (pintype "passive"))
      (node (ref "U11") (pin "1") (pinfunction "S_1") (pintype "passive"))
      (node (ref "U11") (pin "2") (pinfunction "S_2") (pintype "passive"))
      (node (ref "U11") (pin "3") (pinfunction "S_3") (pintype "passive"))
      (node (ref "U15") (pin "5") (pinfunction "D_5") (pintype "passive"))
      (node (ref "U15") (pin "6") (pinfunction "D_6") (pintype "passive"))
      (node (ref "U15") (pin "7") (pinfunction "D_7") (pintype "passive"))
      (node (ref "U15") (pin "8") (pinfunction "D_8") (pintype "passive"))
      (node (ref "U15") (pin "9") (pinfunction "D_9") (pintype "passive"))
      (node (ref "U9") (pin "18") (pinfunction "LX1_18") (pintype "passive"))
    )
    (net (code "139") (name "Net-(U9-LX2)") (class "Default")
      (node (ref "CBSR1") (pin "2") (pinfunction "2_2") (pintype "passive"))
      (node (ref "L3") (pin "2") (pinfunction "2_2") (pintype "passive"))
      (node (ref "RC1") (pin "1") (pinfunction "1_1") (pintype "passive"))
      (node (ref "U12") (pin "1") (pinfunction "S_1") (pintype "passive"))
      (node (ref "U12") (pin "2") (pinfunction "S_2") (pintype "passive"))
      (node (ref "U12") (pin "3") (pinfunction "S_3") (pintype "passive"))
      (node (ref "U14") (pin "5") (pinfunction "D_5") (pintype "passive"))
      (node (ref "U14") (pin "6") (pinfunction "D_6") (pintype "passive"))
      (node (ref "U14") (pin "7") (pinfunction "D_7") (pintype "passive"))
      (node (ref "U14") (pin "8") (pinfunction "D_8") (pintype "passive"))
      (node (ref "U14") (pin "9") (pinfunction "D_9") (pintype "passive"))
      (node (ref "U9") (pin "21") (pinfunction "LX2_21") (pintype "passive"))
    )
    (net (code "140") (name "Net-(U9-NTC)") (class "Default")
      (node (ref "CNTC") (pin "1") (pinfunction "1_1") (pintype "passive"))
      (node (ref "RNTC") (pin "1") (pinfunction "1_1") (pintype "passive"))
      (node (ref "U9") (pin "37") (pinfunction "NTC_37") (pintype "passive"))
    )
    (net (code "141") (name "Net-(U9-PCIN)") (class "Default")
      (node (ref "RSC2") (pin "1") (pinfunction "1_1") (pintype "passive"))
      (node (ref "RSCL1") (pin "1") (pinfunction "1_1") (pintype "passive"))
      (node (ref "U11") (pin "5") (pinfunction "D_5") (pintype "passive"))
      (node (ref "U11") (pin "6") (pinfunction "D_6") (pintype "passive"))
      (node (ref "U11") (pin "7") (pinfunction "D_7") (pintype "passive"))
      (node (ref "U11") (pin "8") (pinfunction "D_8") (pintype "passive"))
      (node (ref "U11") (pin "9") (pinfunction "D_9") (pintype "passive"))
      (node (ref "U9") (pin "15") (pinfunction "PCIN_15") (pintype "passive"))
    )
    (net (code "142") (name "Net-(U9-PCON)") (class "Default")
      (node (ref "RSC1") (pin "1") (pinfunction "1_1") (pintype "passive"))
      (node (ref "RSCR1") (pin "1") (pinfunction "1_1") (pintype "passive"))
      (node (ref "U12") (pin "5") (pinfunction "D_5") (pintype "passive"))
      (node (ref "U12") (pin "6") (pinfunction "D_6") (pintype "passive"))
      (node (ref "U12") (pin "7") (pinfunction "D_7") (pintype "passive"))
      (node (ref "U12") (pin "8") (pinfunction "D_8") (pintype "passive"))
      (node (ref "U12") (pin "9") (pinfunction "D_9") (pintype "passive"))
      (node (ref "U9") (pin "24") (pinfunction "PCON_24") (pintype "passive"))
    )
    (net (code "143") (name "Net-(U9-VCC5V)") (class "Default")
      (node (ref "CVC2") (pin "1") (pinfunction "1_1") (pintype "passive"))
      (node (ref "U9") (pin "29") (pinfunction "VCC5V_29") (pintype "passive"))
    )
    (net (code "144") (name "Net-(U9-VCCIO)") (class "Default")
      (node (ref "CVC1") (pin "1") (pinfunction "1_1") (pintype "passive"))
      (node (ref "U9") (pin "32") (pinfunction "VCCIO_32") (pintype "passive"))
    )
    (net (code "145") (name "Net-(U9-VSET)") (class "Default")
      (node (ref "RVS1") (pin "1") (pinfunction "1_1") (pintype "passive"))
      (node (ref "U9") (pin "35") (pinfunction "VSET_35") (pintype "passive"))
    )
    (net (code "146") (name "Net-(U10-G)") (class "Default")
      (node (ref "U10") (pin "4") (pinfunction "G_4") (pintype "passive"))
      (node (ref "U9") (pin "9") (pinfunction "VBUSG_9") (pintype "passive"))
    )
    (net (code "147") (name "Net-(U11-G)") (class "Default")
      (node (ref "U11") (pin "4") (pinfunction "G_4") (pintype "passive"))
      (node (ref "U9") (pin "16") (pinfunction "HG1_16") (pintype "passive"))
    )
    (net (code "148") (name "Net-(U12-G)") (class "Default")
      (node (ref "U12") (pin "4") (pinfunction "G_4") (pintype "passive"))
      (node (ref "U9") (pin "23") (pinfunction "HG2_23") (pintype "passive"))
    )
    (net (code "149") (name "Net-(U13-BOOT)") (class "Default")
      (node (ref "C37") (pin "2") (pinfunction "2_2") (pintype "passive"))
      (node (ref "U13") (pin "1") (pinfunction "BOOT_1") (pintype "passive"))
    )
    (net (code "150") (name "Net-(U14-G)") (class "Default")
      (node (ref "U14") (pin "4") (pinfunction "G_4") (pintype "passive"))
      (node (ref "U9") (pin "20") (pinfunction "LG2_20") (pintype "passive"))
    )
    (net (code "151") (name "Net-(U15-G)") (class "Default")
      (node (ref "U15") (pin "4") (pinfunction "G_4") (pintype "passive"))
      (node (ref "U9") (pin "19") (pinfunction "LG1_19") (pintype "passive"))
    )
    (net (code "152") (name "Net-(U16-CFG)") (class "Default")
      (node (ref "R58") (pin "1") (pinfunction "1_1") (pintype "passive"))
      (node (ref "U16") (pin "6") (pinfunction "CFG_6") (pintype "passive"))
    )
    (net (code "153") (name "Net-(U16-VCC)") (class "Default")
      (node (ref "C40") (pin "2") (pinfunction "2_2") (pintype "passive"))
      (node (ref "R57") (pin "1") (pinfunction "1_1") (pintype "passive"))
      (node (ref "R58") (pin "2") (pinfunction "2_2") (pintype "passive"))
      (node (ref "U16") (pin "1") (pinfunction "VCC_1") (pintype "passive"))
    )
    (net (code "154") (name "VBUS") (class "Default")
      (node (ref "D1") (pin "1") (pinfunction "A_1") (pintype "passive"))
      (node (ref "TYPE-C1") (pin "A4B9") (pinfunction "VBUS_A4B9") (pintype "passive"))
      (node (ref "TYPE-C1") (pin "B4A9") (pinfunction "VBUS_B4A9") (pintype "passive"))
    )
    (net (code "155") (name "unconnected-(B1-GPIO3-Pad15)") (class "Default")
      (node (ref "B1") (pin "15") (pinfunction "GPIO3_15") (pintype "passive"))
    )
    (net (code "156") (name "unconnected-(B1-GPIO20-Pad14)") (class "Default")
      (node (ref "B1") (pin "14") (pinfunction "GPIO20_14") (pintype "passive"))
    )
    (net (code "157") (name "unconnected-(B1-GPIO21-Pad23)") (class "Default")
      (node (ref "B1") (pin "23") (pinfunction "GPIO21_23") (pintype "passive"))
    )
    (net (code "158") (name "unconnected-(B1-GPIO45-Pad26)") (class "Default")
      (node (ref "B1") (pin "26") (pinfunction "GPIO45_26") (pintype "passive"))
    )
    (net (code "159") (name "unconnected-(B1-GPIO46-Pad16)") (class "Default")
      (node (ref "B1") (pin "16") (pinfunction "GPIO46_16") (pintype "passive"))
    )
    (net (code "160") (name "unconnected-(B1-GPIO47-Pad24)") (class "Default")
      (node (ref "B1") (pin "24") (pinfunction "GPIO47_24") (pintype "passive"))
    )
    (net (code "161") (name "unconnected-(B1-GPIO48-Pad25)") (class "Default")
      (node (ref "B1") (pin "25") (pinfunction "GPIO48_25") (pintype "passive"))
    )
    (net (code "162") (name "unconnected-(B1-IO1-Pad39)") (class "Default")
      (node (ref "B1") (pin "39") (pinfunction "IO1_39") (pintype "passive"))
    )
    (net (code "163") (name "unconnected-(B1-IO2-Pad38)") (class "Default")
      (node (ref "B1") (pin "38") (pinfunction "IO2_38") (pintype "passive"))
    )
    (net (code "164") (name "unconnected-(TYPE-C1-SBU1-PadA8)") (class "Default")
      (node (ref "TYPE-C1") (pin "A8") (pinfunction "SBU1_A8") (pintype "passive+no_connect"))
    )
    (net (code "165") (name "unconnected-(TYPE-C1-SBU2-PadB8)") (class "Default")
      (node (ref "TYPE-C1") (pin "B8") (pinfunction "SBU2_B8") (pintype "passive+no_connect"))
    )
    (net (code "166") (name "unconnected-(TYPE-C2-SBU1-PadA8)") (class "Default")
      (node (ref "TYPE-C2") (pin "A8") (pinfunction "SBU1_A8") (pintype "passive+no_connect"))
    )
    (net (code "167") (name "unconnected-(TYPE-C2-SBU2-PadB8)") (class "Default")
      (node (ref "TYPE-C2") (pin "B8") (pinfunction "SBU2_B8") (pintype "passive+no_connect"))
    )
    (net (code "168") (name "unconnected-(TYPE-C3-DN1-PadA7)") (class "Default")
      (node (ref "TYPE-C3") (pin "A7") (pinfunction "DN1_A7") (pintype "passive+no_connect"))
    )
    (net (code "169") (name "unconnected-(TYPE-C3-DN2-PadB7)") (class "Default")
      (node (ref "TYPE-C3") (pin "B7") (pinfunction "DN2_B7") (pintype "passive+no_connect"))
    )
    (net (code "170") (name "unconnected-(TYPE-C3-DP1-PadA6)") (class "Default")
      (node (ref "TYPE-C3") (pin "A6") (pinfunction "DP1_A6") (pintype "passive+no_connect"))
    )
    (net (code "171") (name "unconnected-(TYPE-C3-DP2-PadB6)") (class "Default")
      (node (ref "TYPE-C3") (pin "B6") (pinfunction "DP2_B6") (pintype "passive+no_connect"))
    )
    (net (code "172") (name "unconnected-(TYPE-C3-SBU1-PadA8)") (class "Default")
      (node (ref "TYPE-C3") (pin "A8") (pinfunction "SBU1_A8") (pintype "passive+no_connect"))
    )
    (net (code "173") (name "unconnected-(TYPE-C3-SBU2-PadB8)") (class "Default")
      (node (ref "TYPE-C3") (pin "B8") (pinfunction "SBU2_B8") (pintype "passive+no_connect"))
    )
    (net (code "174") (name "unconnected-(U1-NC-Pad2)") (class "Default")
      (node (ref "U1") (pin "2") (pinfunction "NC_2") (pintype "passive+no_connect"))
    )
    (net (code "175") (name "unconnected-(U1-NC-Pad3)") (class "Default")
      (node (ref "U1") (pin "3") (pinfunction "NC_3") (pintype "passive+no_connect"))
    )
    (net (code "176") (name "unconnected-(U3-CTS#-Pad9)") (class "Default")
      (node (ref "U3") (pin "9") (pinfunction "CTS#_9") (pintype "passive+no_connect"))
    )
    (net (code "177") (name "unconnected-(U3-DCD#-Pad12)") (class "Default")
      (node (ref "U3") (pin "12") (pinfunction "DCD#_12") (pintype "passive+no_connect"))
    )
    (net (code "178") (name "unconnected-(U3-DSR#-Pad10)") (class "Default")
      (node (ref "U3") (pin "10") (pinfunction "DSR#_10") (pintype "passive+no_connect"))
    )
    (net (code "179") (name "unconnected-(U3-R232-Pad15)") (class "Default")
      (node (ref "U3") (pin "15") (pinfunction "R232_15") (pintype "passive"))
    )
    (net (code "180") (name "unconnected-(U3-RI#-Pad11)") (class "Default")
      (node (ref "U3") (pin "11") (pinfunction "RI#_11") (pintype "passive+no_connect"))
    )
    (net (code "181") (name "unconnected-(U3-X1-Pad7)") (class "Default")
      (node (ref "U3") (pin "7") (pinfunction "X1_7") (pintype "passive+no_connect"))
    )
    (net (code "182") (name "unconnected-(U3-X2-Pad8)") (class "Default")
      (node (ref "U3") (pin "8") (pinfunction "X2_8") (pintype "passive+no_connect"))
    )
    (net (code "183") (name "unconnected-(U6-EN-Pad5)") (class "Default")
      (node (ref "U6") (pin "5") (pinfunction "EN_5") (pintype "passive+no_connect"))
    )
    (net (code "184") (name "unconnected-(U6-NC-Pad2)") (class "Default")
      (node (ref "U6") (pin "2") (pinfunction "NC_2") (pintype "passive+no_connect"))
    )
    (net (code "185") (name "unconnected-(U6-NC-Pad3)") (class "Default")
      (node (ref "U6") (pin "3") (pinfunction "NC_3") (pintype "passive+no_connect"))
    )
    (net (code "186") (name "unconnected-(U8-GAIN-Pad2)") (class "Default")
      (node (ref "U8") (pin "2") (pinfunction "GAIN_2") (pintype "passive+no_connect"))
    )
    (net (code "187") (name "unconnected-(U9-LT-Pad2)") (class "Default")
      (node (ref "U9") (pin "2") (pinfunction "LT_2") (pintype "passive+no_connect"))
    )
    (net (code "188") (name "unconnected-(U9-LX-Pad28)") (class "Default")
      (node (ref "U9") (pin "28") (pinfunction "LX_28") (pintype "passive+no_connect"))
    )
    (net (code "189") (name "unconnected-(U9-NC-Pad1)") (class "Default")
      (node (ref "U9") (pin "1") (pinfunction "NC_1") (pintype "passive+no_connect"))
    )
    (net (code "190") (name "unconnected-(U9-NC-Pad3)") (class "Default")
      (node (ref "U9") (pin "3") (pinfunction "NC_3") (pintype "passive+no_connect"))
    )
    (net (code "191") (name "unconnected-(U9-NC-Pad6)") (class "Default")
      (node (ref "U9") (pin "6") (pinfunction "NC_6") (pintype "passive+no_connect"))
    )
    (net (code "192") (name "unconnected-(U9-NC-Pad7)") (class "Default")
      (node (ref "U9") (pin "7") (pinfunction "NC_7") (pintype "passive+no_connect"))
    )
    (net (code "193") (name "unconnected-(U9-NC-Pad44)") (class "Default")
      (node (ref "U9") (pin "44") (pinfunction "NC_44") (pintype "passive+no_connect"))
    )
    (net (code "194") (name "unconnected-(U9-NC-Pad45)") (class "Default")
      (node (ref "U9") (pin "45") (pinfunction "NC_45") (pintype "passive+no_connect"))
    )
    (net (code "195") (name "unconnected-(U9-NC-Pad48)") (class "Default")
      (node (ref "U9") (pin "48") (pinfunction "NC_48") (pintype "passive+no_connect"))
    )
    (net (code "196") (name "unconnected-(U9-NV-Pad31)") (class "Default")
      (node (ref "U9") (pin "31") (pinfunction "NV_31") (pintype "passive+no_connect"))
    )
    (net (code "197") (name "unconnected-(U13-EN-Pad5)") (class "Default")
      (node (ref "U13") (pin "5") (pinfunction "EN_5") (pintype "passive+no_connect"))
    )
    (net (code "198") (name "unconnected-(U13-NC-Pad2)") (class "Default")
      (node (ref "U13") (pin "2") (pinfunction "NC_2") (pintype "passive+no_connect"))
    )
    (net (code "199") (name "unconnected-(U13-NC-Pad3)") (class "Default")
      (node (ref "U13") (pin "3") (pinfunction "NC_3") (pintype "passive+no_connect"))
    )
    (net (code "200") (name "unconnected-(U16-PG-Pad3)") (class "Default")
      (node (ref "U16") (pin "3") (pinfunction "PG_3") (pintype "passive+no_connect"))
    )
  )
)
